# ASCII_15_BoardPowerSupply.net
KiCad netlist of a schematic drawn in Altium Designer
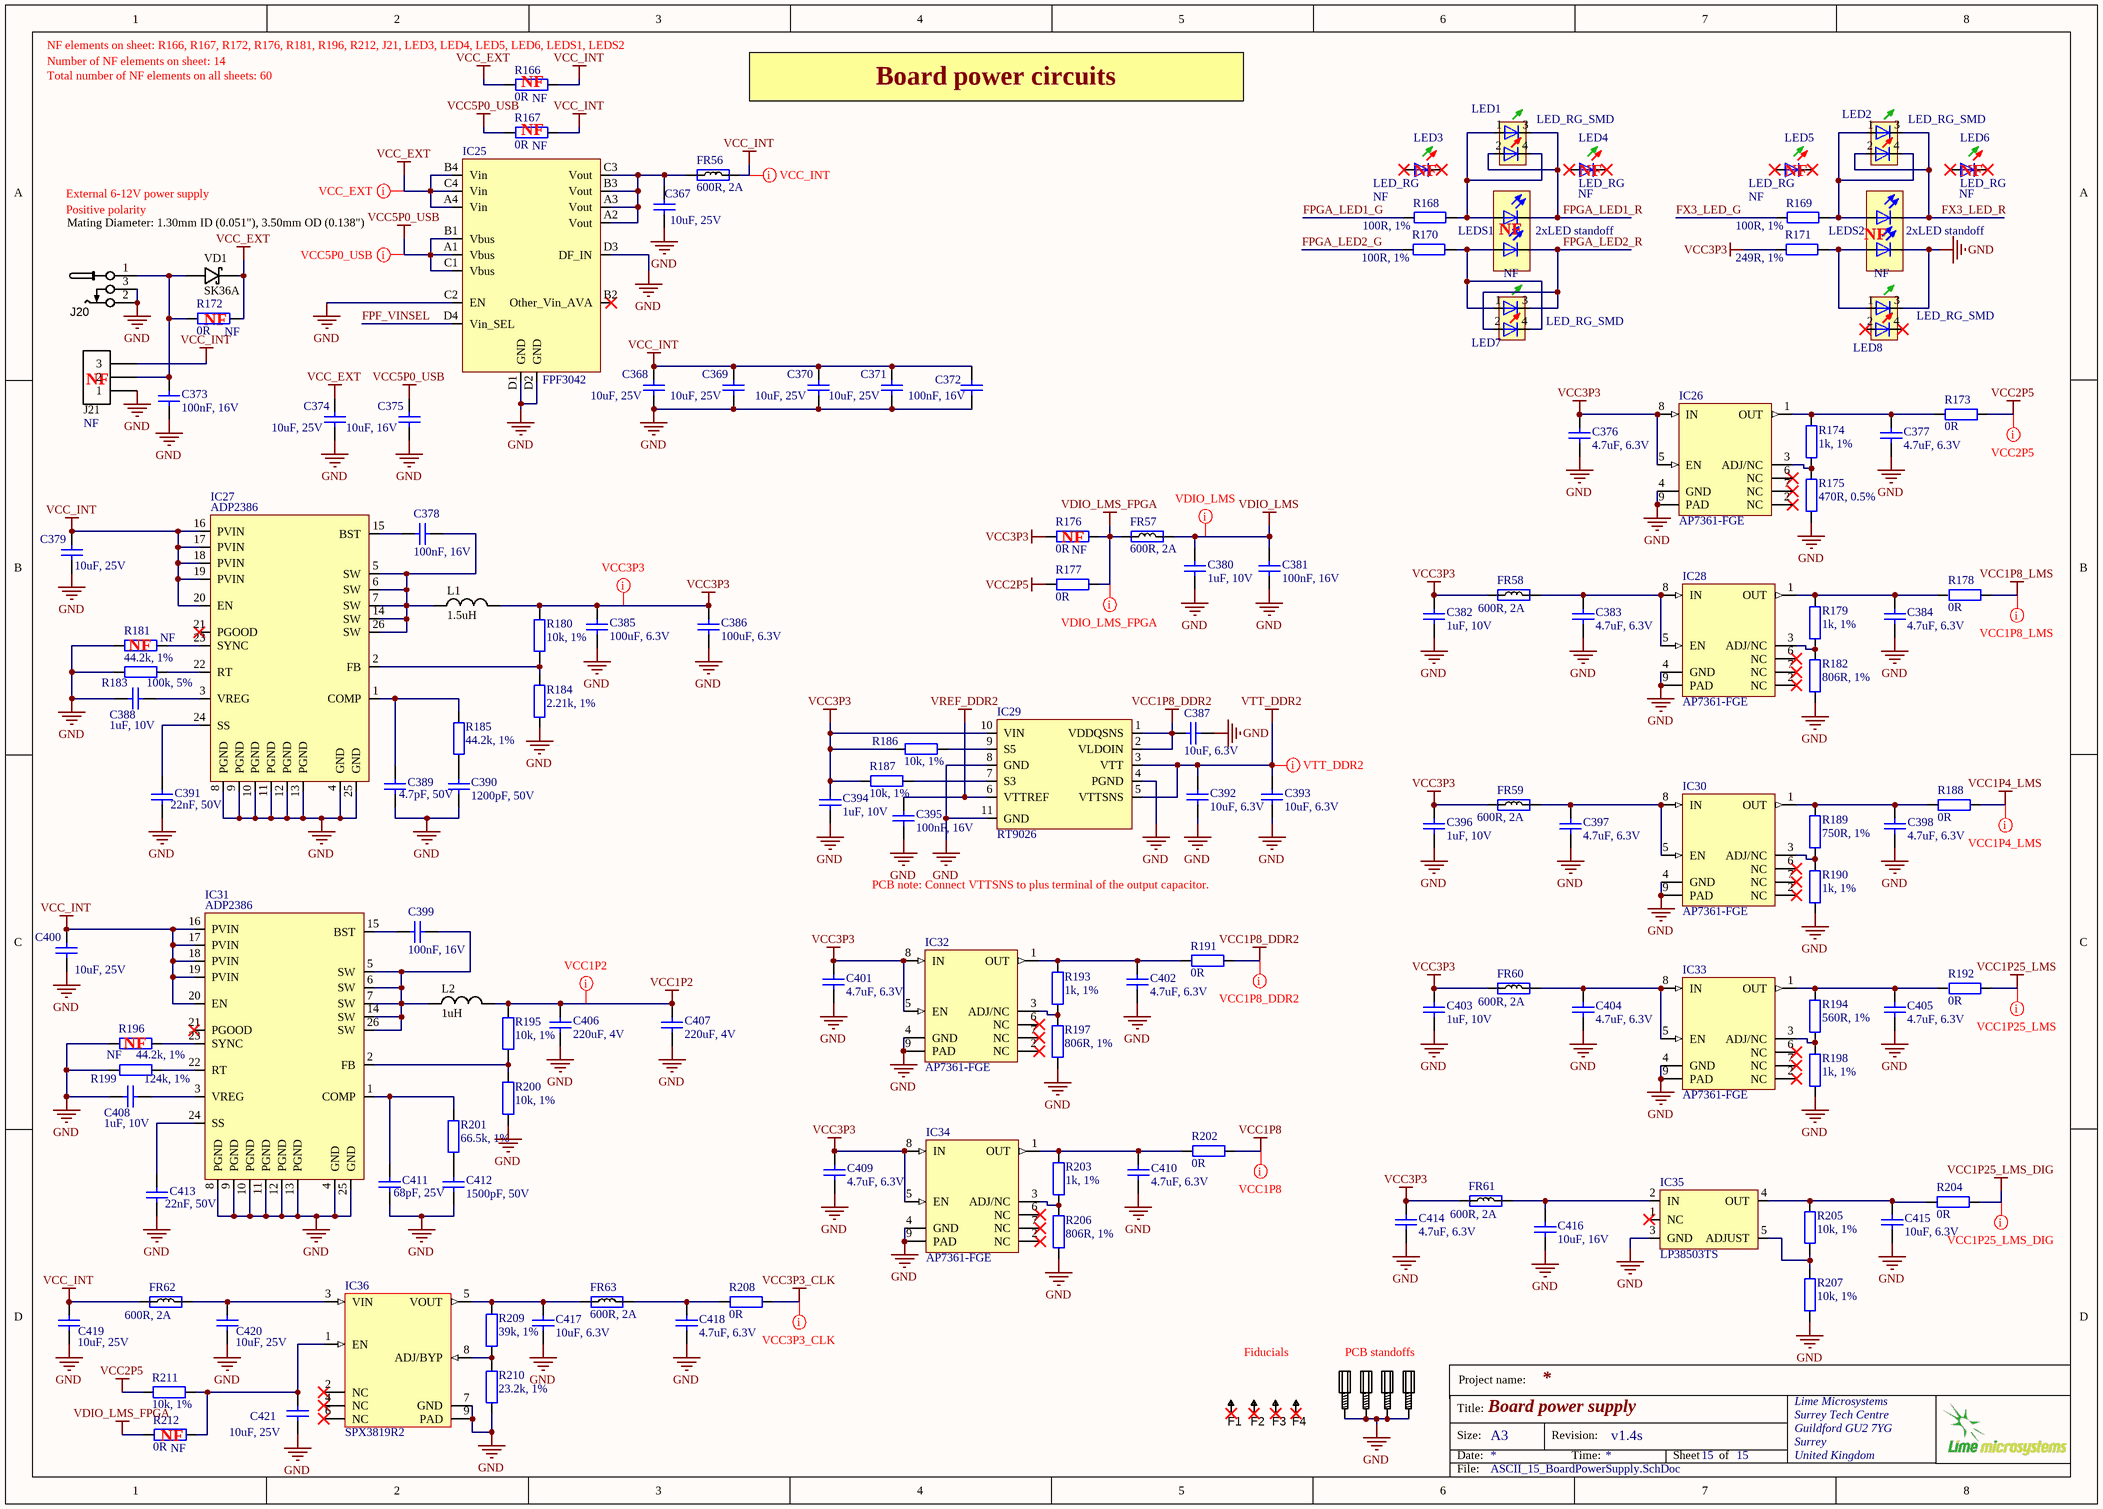
[diagram p0: ASCII_15_BoardPowerSupply.SchDoc]

(export (version "E")
  (design (tool "Eeschema 10.0.6"))
  (components
    (comp (ref "C367")
      (value "10uF, 25V")
      (footprint "CAP0603")
      (fields
        (field (name "MANUFACTURER") "Murata Electronics North America")
        (field (name "MANUFACTURER PART NUMBER") "GRM188R61E106MA73D")
        (field (name "TOLERANCE") "±20%")
      )
      (libsource (lib "LimeMicroAltiumLib_schLib") (part "Cap_0603"))
    )
    (comp (ref "C368")
      (value "10uF, 25V")
      (footprint "CAP0603")
      (fields
        (field (name "MANUFACTURER") "Murata Electronics North America")
        (field (name "MANUFACTURER PART NUMBER") "GRM188R61E106MA73D")
        (field (name "TOLERANCE") "±20%")
      )
      (libsource (lib "LimeMicroAltiumLib_schLib") (part "Cap_0603"))
    )
    (comp (ref "C369")
      (value "10uF, 25V")
      (footprint "CAP0603")
      (fields
        (field (name "MANUFACTURER") "Murata Electronics North America")
        (field (name "MANUFACTURER PART NUMBER") "GRM188R61E106MA73D")
        (field (name "TOLERANCE") "±20%")
      )
      (libsource (lib "LimeMicroAltiumLib_schLib") (part "Cap_0603"))
    )
    (comp (ref "C370")
      (value "10uF, 25V")
      (footprint "CAP0603")
      (fields
        (field (name "MANUFACTURER") "Murata Electronics North America")
        (field (name "MANUFACTURER PART NUMBER") "GRM188R61E106MA73D")
        (field (name "TOLERANCE") "±20%")
      )
      (libsource (lib "LimeMicroAltiumLib_schLib") (part "Cap_0603"))
    )
    (comp (ref "C371")
      (value "10uF, 25V")
      (footprint "CAP0603")
      (fields
        (field (name "MANUFACTURER") "Murata Electronics North America")
        (field (name "MANUFACTURER PART NUMBER") "GRM188R61E106MA73D")
        (field (name "TOLERANCE") "±20%")
      )
      (libsource (lib "LimeMicroAltiumLib_schLib") (part "Cap_0603"))
    )
    (comp (ref "C372")
      (value "100nF, 16V")
      (footprint "CAP0402")
      (fields
        (field (name "MANUFACTURER") "Murata Electronics")
        (field (name "TOLERANCE") "10 %")
        (field (name "MANUFACTURER PART NUMBER") "GRM155R71C104KA88D")
      )
      (libsource (lib "LimeMicroAltiumLib_schLib") (part "Cap_0402"))
    )
    (comp (ref "C373")
      (value "100nF, 16V")
      (footprint "CAP0402")
      (fields
        (field (name "MANUFACTURER") "Murata Electronics")
        (field (name "TOLERANCE") "10 %")
        (field (name "MANUFACTURER PART NUMBER") "GRM155R71C104KA88D")
      )
      (libsource (lib "LimeMicroAltiumLib_schLib") (part "Cap_0402"))
    )
    (comp (ref "C374")
      (value "10uF, 25V")
      (footprint "CAP0603")
      (fields
        (field (name "MANUFACTURER") "Murata Electronics North America")
        (field (name "MANUFACTURER PART NUMBER") "GRM188R61E106MA73D")
        (field (name "TOLERANCE") "±20%")
      )
      (libsource (lib "LimeMicroAltiumLib_schLib") (part "Cap_0603"))
    )
    (comp (ref "C375")
      (value "10uF, 16V")
      (footprint "CAP0603")
      (fields (field (name "MANUFACTURER") "Yageo") (field (name "TOLERANCE") "±20%"))
      (libsource (lib "LimeMicroAltiumLib_schLib") (part "Cap_0603"))
    )
    (comp (ref "C376")
      (value "4.7uF, 6.3V")
      (footprint "CAP0402")
      (fields
        (field (name "MANUFACTURER") "Murata Electronics North America")
        (field (name "TOLERANCE") "±20%")
        (field (name "MANUFACTURER PART NUMBER") "GRM155R60J475ME87D")
      )
      (libsource (lib "LimeMicroAltiumLib_schLib") (part "Cap_0402"))
    )
    (comp (ref "C377")
      (value "4.7uF, 6.3V")
      (footprint "CAP0402")
      (fields
        (field (name "MANUFACTURER") "Murata Electronics North America")
        (field (name "TOLERANCE") "±20%")
        (field (name "MANUFACTURER PART NUMBER") "GRM155R60J475ME87D")
      )
      (libsource (lib "LimeMicroAltiumLib_schLib") (part "Cap_0402"))
    )
    (comp (ref "C378")
      (value "100nF, 16V")
      (footprint "CAP0402")
      (fields
        (field (name "MANUFACTURER") "Murata Electronics")
        (field (name "TOLERANCE") "10 %")
        (field (name "MANUFACTURER PART NUMBER") "GRM155R71C104KA88D")
      )
      (libsource (lib "LimeMicroAltiumLib_schLib") (part "Cap_0402"))
    )
    (comp (ref "C379")
      (value "10uF, 25V")
      (footprint "CAP0603")
      (fields
        (field (name "MANUFACTURER") "Murata Electronics North America")
        (field (name "MANUFACTURER PART NUMBER") "GRM188R61E106MA73D")
        (field (name "TOLERANCE") "±20%")
      )
      (libsource (lib "LimeMicroAltiumLib_schLib") (part "Cap_0603"))
    )
    (comp (ref "C380")
      (value "1uF, 10V")
      (footprint "CAP0402")
      (fields (field (name "MANUFACTURER") "TDK"))
      (libsource (lib "LimeMicroAltiumLib_schLib") (part "Cap_0402"))
    )
    (comp (ref "C381")
      (value "100nF, 16V")
      (footprint "CAP0402")
      (fields
        (field (name "MANUFACTURER") "Murata Electronics")
        (field (name "TOLERANCE") "10 %")
        (field (name "MANUFACTURER PART NUMBER") "GRM155R71C104KA88D")
      )
      (libsource (lib "LimeMicroAltiumLib_schLib") (part "Cap_0402"))
    )
    (comp (ref "C382")
      (value "1uF, 10V")
      (footprint "CAP0402")
      (fields (field (name "MANUFACTURER") "TDK"))
      (libsource (lib "LimeMicroAltiumLib_schLib") (part "Cap_0402"))
    )
    (comp (ref "C383")
      (value "4.7uF, 6.3V")
      (footprint "CAP0402")
      (fields
        (field (name "MANUFACTURER") "Murata Electronics North America")
        (field (name "TOLERANCE") "±20%")
        (field (name "MANUFACTURER PART NUMBER") "GRM155R60J475ME87D")
      )
      (libsource (lib "LimeMicroAltiumLib_schLib") (part "Cap_0402"))
    )
    (comp (ref "C384")
      (value "4.7uF, 6.3V")
      (footprint "CAP0402")
      (fields
        (field (name "MANUFACTURER") "Murata Electronics North America")
        (field (name "TOLERANCE") "±20%")
        (field (name "MANUFACTURER PART NUMBER") "GRM155R60J475ME87D")
      )
      (libsource (lib "LimeMicroAltiumLib_schLib") (part "Cap_0402"))
    )
    (comp (ref "C385")
      (value "100uF, 6.3V")
      (footprint "CAP1206")
      (fields (field (name "MANUFACTURER") "Murata Electronics North America"))
      (libsource (lib "LimeFPGAboard_schLib") (part "Cap_1206"))
    )
    (comp (ref "C386")
      (value "100uF, 6.3V")
      (footprint "CAP1206")
      (fields (field (name "MANUFACTURER") "Murata Electronics North America"))
      (libsource (lib "LimeFPGAboard_schLib") (part "Cap_1206"))
    )
    (comp (ref "C387")
      (value "10uF, 6.3V")
      (footprint "CAP0603")
      (fields (field (name "TOLERANCE") "±20%") (field (name "MANUFACTURER") "Yageo"))
      (libsource (lib "LimeFPGAboard_schLib") (part "Cap_0603"))
    )
    (comp (ref "C388")
      (value "1uF, 10V")
      (footprint "CAP0402")
      (fields (field (name "MANUFACTURER") "TDK"))
      (libsource (lib "LimeMicroAltiumLib_schLib") (part "Cap_0402"))
    )
    (comp (ref "C389")
      (value "4.7pF, 50V")
      (footprint "CAP0402")
      (fields (field (name "MANUFACTURER") "Murata Electronics North America"))
      (libsource (lib "LimeMicroAltiumLib_schLib") (part "Cap_0402"))
    )
    (comp (ref "C390")
      (value "1200pF, 50V")
      (footprint "CAP0402")
      (fields (field (name "MANUFACTURER") "Kemet") (field (name "TOLERANCE") "±5%"))
      (libsource (lib "LimeMicroAltiumLib_schLib") (part "Cap_0402"))
    )
    (comp (ref "C391")
      (value "22nF, 50V")
      (footprint "CAP0402")
      (fields (field (name "TOLERANCE") "±10%") (field (name "MANUFACTURER") "Kemet"))
      (libsource (lib "LimeMicroAltiumLib_schLib") (part "Cap_0402"))
    )
    (comp (ref "C392")
      (value "10uF, 6.3V")
      (footprint "CAP0603")
      (fields (field (name "TOLERANCE") "±20%") (field (name "MANUFACTURER") "Yageo"))
      (libsource (lib "LimeFPGAboard_schLib") (part "Cap_0603"))
    )
    (comp (ref "C393")
      (value "10uF, 6.3V")
      (footprint "CAP0603")
      (fields (field (name "TOLERANCE") "±20%") (field (name "MANUFACTURER") "Yageo"))
      (libsource (lib "LimeFPGAboard_schLib") (part "Cap_0603"))
    )
    (comp (ref "C394")
      (value "1uF, 10V")
      (footprint "CAP0402")
      (fields (field (name "MANUFACTURER") "TDK"))
      (libsource (lib "LimeMicroAltiumLib_schLib") (part "Cap_0402"))
    )
    (comp (ref "C395")
      (value "100nF, 16V")
      (footprint "CAP0402")
      (fields
        (field (name "MANUFACTURER") "Murata Electronics")
        (field (name "TOLERANCE") "10 %")
        (field (name "MANUFACTURER PART NUMBER") "GRM155R71C104KA88D")
      )
      (libsource (lib "LimeMicroAltiumLib_schLib") (part "Cap_0402"))
    )
    (comp (ref "C396")
      (value "1uF, 10V")
      (footprint "CAP0402")
      (fields (field (name "MANUFACTURER") "TDK"))
      (libsource (lib "LimeMicroAltiumLib_schLib") (part "Cap_0402"))
    )
    (comp (ref "C397")
      (value "4.7uF, 6.3V")
      (footprint "CAP0402")
      (fields
        (field (name "MANUFACTURER") "Murata Electronics North America")
        (field (name "TOLERANCE") "±20%")
        (field (name "MANUFACTURER PART NUMBER") "GRM155R60J475ME87D")
      )
      (libsource (lib "LimeMicroAltiumLib_schLib") (part "Cap_0402"))
    )
    (comp (ref "C398")
      (value "4.7uF, 6.3V")
      (footprint "CAP0402")
      (fields
        (field (name "MANUFACTURER") "Murata Electronics North America")
        (field (name "TOLERANCE") "±20%")
        (field (name "MANUFACTURER PART NUMBER") "GRM155R60J475ME87D")
      )
      (libsource (lib "LimeMicroAltiumLib_schLib") (part "Cap_0402"))
    )
    (comp (ref "C399")
      (value "100nF, 16V")
      (footprint "CAP0402")
      (fields
        (field (name "MANUFACTURER") "Murata Electronics")
        (field (name "TOLERANCE") "10 %")
        (field (name "MANUFACTURER PART NUMBER") "GRM155R71C104KA88D")
      )
      (libsource (lib "LimeMicroAltiumLib_schLib") (part "Cap_0402"))
    )
    (comp (ref "C400")
      (value "10uF, 25V")
      (footprint "CAP0603")
      (fields
        (field (name "MANUFACTURER") "Murata Electronics North America")
        (field (name "MANUFACTURER PART NUMBER") "GRM188R61E106MA73D")
        (field (name "TOLERANCE") "±20%")
      )
      (libsource (lib "LimeMicroAltiumLib_schLib") (part "Cap_0603"))
    )
    (comp (ref "C401")
      (value "4.7uF, 6.3V")
      (footprint "CAP0402")
      (fields
        (field (name "MANUFACTURER") "Murata Electronics North America")
        (field (name "TOLERANCE") "±20%")
        (field (name "MANUFACTURER PART NUMBER") "GRM155R60J475ME87D")
      )
      (libsource (lib "LimeMicroAltiumLib_schLib") (part "Cap_0402"))
    )
    (comp (ref "C402")
      (value "4.7uF, 6.3V")
      (footprint "CAP0402")
      (fields
        (field (name "MANUFACTURER") "Murata Electronics North America")
        (field (name "TOLERANCE") "±20%")
        (field (name "MANUFACTURER PART NUMBER") "GRM155R60J475ME87D")
      )
      (libsource (lib "LimeMicroAltiumLib_schLib") (part "Cap_0402"))
    )
    (comp (ref "C403")
      (value "1uF, 10V")
      (footprint "CAP0402")
      (fields (field (name "MANUFACTURER") "TDK"))
      (libsource (lib "LimeMicroAltiumLib_schLib") (part "Cap_0402"))
    )
    (comp (ref "C404")
      (value "4.7uF, 6.3V")
      (footprint "CAP0402")
      (fields
        (field (name "MANUFACTURER") "Murata Electronics North America")
        (field (name "TOLERANCE") "±20%")
        (field (name "MANUFACTURER PART NUMBER") "GRM155R60J475ME87D")
      )
      (libsource (lib "LimeMicroAltiumLib_schLib") (part "Cap_0402"))
    )
    (comp (ref "C405")
      (value "4.7uF, 6.3V")
      (footprint "CAP0402")
      (fields
        (field (name "MANUFACTURER") "Murata Electronics North America")
        (field (name "TOLERANCE") "±20%")
        (field (name "MANUFACTURER PART NUMBER") "GRM155R60J475ME87D")
      )
      (libsource (lib "LimeMicroAltiumLib_schLib") (part "Cap_0402"))
    )
    (comp (ref "C406")
      (value "220uF, 4V")
      (footprint "CAP1206")
      (fields
        (field (name "MANUFACTURER") "Murata Electronics North America")
        (field (name "TOLERANCE") "±20%")
        (field (name "MANUFACTURER PART NUMBER") "GRM31CR60G227ME11L")
      )
      (libsource (lib "LimeFPGAboard_schLib") (part "Cap_1206"))
    )
    (comp (ref "C407")
      (value "220uF, 4V")
      (footprint "CAP1206")
      (fields
        (field (name "MANUFACTURER") "Murata Electronics North America")
        (field (name "TOLERANCE") "±20%")
        (field (name "MANUFACTURER PART NUMBER") "GRM31CR60G227ME11L")
      )
      (libsource (lib "LimeFPGAboard_schLib") (part "Cap_1206"))
    )
    (comp (ref "C408")
      (value "1uF, 10V")
      (footprint "CAP0402")
      (fields (field (name "MANUFACTURER") "TDK"))
      (libsource (lib "LimeMicroAltiumLib_schLib") (part "Cap_0402"))
    )
    (comp (ref "C409")
      (value "4.7uF, 6.3V")
      (footprint "CAP0402")
      (fields
        (field (name "MANUFACTURER") "Murata Electronics North America")
        (field (name "TOLERANCE") "±20%")
        (field (name "MANUFACTURER PART NUMBER") "GRM155R60J475ME87D")
      )
      (libsource (lib "LimeMicroAltiumLib_schLib") (part "Cap_0402"))
    )
    (comp (ref "C410")
      (value "4.7uF, 6.3V")
      (footprint "CAP0402")
      (fields
        (field (name "MANUFACTURER") "Murata Electronics North America")
        (field (name "TOLERANCE") "±20%")
        (field (name "MANUFACTURER PART NUMBER") "GRM155R60J475ME87D")
      )
      (libsource (lib "LimeMicroAltiumLib_schLib") (part "Cap_0402"))
    )
    (comp (ref "C411")
      (value "68pF, 25V")
      (footprint "CAP0402")
      (fields (field (name "TOLERANCE") "±1%") (field (name "MANUFACTURER") "Kemet"))
      (libsource (lib "LimeMicroAltiumLib_schLib") (part "Cap_0402"))
    )
    (comp (ref "C412")
      (value "1500pF, 50V")
      (footprint "CAP0402")
      (fields
        (field (name "MANUFACTURER") "Samsung Electro-Mechanics America, Inc.")
        (field (name "TOLERANCE") "±10%")
      )
      (libsource (lib "LimeMicroAltiumLib_schLib") (part "Cap_0402"))
    )
    (comp (ref "C413")
      (value "22nF, 50V")
      (footprint "CAP0402")
      (fields (field (name "TOLERANCE") "±10%") (field (name "MANUFACTURER") "Kemet"))
      (libsource (lib "LimeMicroAltiumLib_schLib") (part "Cap_0402"))
    )
    (comp (ref "C414")
      (value "4.7uF, 6.3V")
      (footprint "CAP0402")
      (fields
        (field (name "MANUFACTURER") "Murata Electronics North America")
        (field (name "TOLERANCE") "±20%")
        (field (name "MANUFACTURER PART NUMBER") "GRM155R60J475ME87D")
      )
      (libsource (lib "LimeMicroAltiumLib_schLib") (part "Cap_0402"))
    )
    (comp (ref "C415")
      (value "10uF, 6.3V")
      (footprint "CAP0603")
      (fields (field (name "TOLERANCE") "±20%") (field (name "MANUFACTURER") "Yageo"))
      (libsource (lib "LimeFPGAboard_schLib") (part "Cap_0603"))
    )
    (comp (ref "C416")
      (value "10uF, 16V")
      (footprint "CAP0603")
      (fields (field (name "MANUFACTURER") "Yageo") (field (name "TOLERANCE") "±20%"))
      (libsource (lib "LimeMicroAltiumLib_schLib") (part "Cap_0603"))
    )
    (comp (ref "C417")
      (value "10uF, 6.3V")
      (footprint "CAP0603")
      (fields (field (name "TOLERANCE") "±20%") (field (name "MANUFACTURER") "Yageo"))
      (libsource (lib "LimeFPGAboard_schLib") (part "Cap_0603"))
    )
    (comp (ref "C418")
      (value "4.7uF, 6.3V")
      (footprint "CAP0402")
      (fields
        (field (name "MANUFACTURER") "Murata Electronics North America")
        (field (name "TOLERANCE") "±20%")
        (field (name "MANUFACTURER PART NUMBER") "GRM155R60J475ME87D")
      )
      (libsource (lib "LimeMicroAltiumLib_schLib") (part "Cap_0402"))
    )
    (comp (ref "C419")
      (value "10uF, 25V")
      (footprint "CAP0603")
      (fields
        (field (name "MANUFACTURER") "Murata Electronics North America")
        (field (name "MANUFACTURER PART NUMBER") "GRM188R61E106MA73D")
        (field (name "TOLERANCE") "±20%")
      )
      (libsource (lib "LimeMicroAltiumLib_schLib") (part "Cap_0603"))
    )
    (comp (ref "C420")
      (value "10uF, 25V")
      (footprint "CAP0603")
      (fields
        (field (name "MANUFACTURER") "Murata Electronics North America")
        (field (name "MANUFACTURER PART NUMBER") "GRM188R61E106MA73D")
        (field (name "TOLERANCE") "±20%")
      )
      (libsource (lib "LimeMicroAltiumLib_schLib") (part "Cap_0603"))
    )
    (comp (ref "C421")
      (value "10uF, 25V")
      (footprint "CAP0603")
      (fields
        (field (name "MANUFACTURER") "Murata Electronics North America")
        (field (name "MANUFACTURER PART NUMBER") "GRM188R61E106MA73D")
        (field (name "TOLERANCE") "±20%")
      )
      (libsource (lib "LimeMicroAltiumLib_schLib") (part "Cap_0603"))
    )
    (comp (ref "F1")
      (value "Fiducial")
      (footprint "Fiducial")
      (libsource (lib "VGTU_Altium_lib") (part "Fiducial"))
    )
    (comp (ref "F2")
      (value "Fiducial")
      (footprint "Fiducial")
      (libsource (lib "VGTU_Altium_lib") (part "Fiducial"))
    )
    (comp (ref "F3")
      (value "Fiducial")
      (footprint "Fiducial")
      (libsource (lib "VGTU_Altium_lib") (part "Fiducial"))
    )
    (comp (ref "F4")
      (value "Fiducial")
      (footprint "Fiducial")
      (libsource (lib "VGTU_Altium_lib") (part "Fiducial"))
    )
    (comp (ref "FR56")
      (value "600R, 2A")
      (footprint "RES0805")
      (fields (field (name "MANUFACTURER") "TDK Corporation"))
      (libsource (lib "LimeFPGAboard_schLib") (part "Ferrite"))
    )
    (comp (ref "FR57")
      (value "600R, 2A")
      (footprint "RES0805")
      (fields (field (name "MANUFACTURER") "TDK Corporation"))
      (libsource (lib "LimeMicroAltiumLib_schLib") (part "Ferrite"))
    )
    (comp (ref "FR58")
      (value "600R, 2A")
      (footprint "RES0805")
      (fields (field (name "MANUFACTURER") "TDK Corporation"))
      (libsource (lib "LimeMicroAltiumLib_schLib") (part "Ferrite"))
    )
    (comp (ref "FR59")
      (value "600R, 2A")
      (footprint "RES0805")
      (fields (field (name "MANUFACTURER") "TDK Corporation"))
      (libsource (lib "LimeMicroAltiumLib_schLib") (part "Ferrite"))
    )
    (comp (ref "FR60")
      (value "600R, 2A")
      (footprint "RES0805")
      (fields (field (name "MANUFACTURER") "TDK Corporation"))
      (libsource (lib "LimeMicroAltiumLib_schLib") (part "Ferrite"))
    )
    (comp (ref "FR61")
      (value "600R, 2A")
      (footprint "RES0805")
      (fields (field (name "MANUFACTURER") "TDK Corporation"))
      (libsource (lib "LimeMicroAltiumLib_schLib") (part "Ferrite"))
    )
    (comp (ref "FR62")
      (value "600R, 2A")
      (footprint "RES0805")
      (fields (field (name "MANUFACTURER") "TDK Corporation"))
      (libsource (lib "LimeMicroAltiumLib_schLib") (part "Ferrite"))
    )
    (comp (ref "FR63")
      (value "600R, 2A")
      (footprint "RES0805")
      (fields (field (name "MANUFACTURER") "TDK Corporation"))
      (libsource (lib "LimeMicroAltiumLib_schLib") (part "Ferrite"))
    )
    (comp (ref "IC25")
      (value "FPF3042")
      (footprint "FPF3042")
      (fields (field (name "MANUFACTURER") "Fairchild Semiconductor"))
      (libsource (lib "LimeMicroAltiumLib_schLib") (part "FPF3042"))
    )
    (comp (ref "IC26")
      (value "AP7361-FGE")
      (footprint "AP7361")
      (fields
        (field (name "MANUFACTURER PART NUMBER") "AP7361-FGE-7")
        (field (name "MANUFACTURER") "Diodes Incorporated")
      )
      (libsource (lib "LimeMicroAltiumLib_schLib") (part "AP7361"))
    )
    (comp (ref "IC27")
      (value "ADP2386")
      (footprint "ADP2386")
      (fields
        (field (name "MANUFACTURER PART NUMBER") "ADP2386ACPZN-R7")
        (field (name "MANUFACTURER") "Analog Devices Inc.")
      )
      (libsource (lib "LimeMicroAltiumLib_schLib") (part "ADP2386"))
    )
    (comp (ref "IC28")
      (value "AP7361-FGE")
      (footprint "AP7361")
      (fields
        (field (name "MANUFACTURER PART NUMBER") "AP7361-FGE-7")
        (field (name "MANUFACTURER") "Diodes Incorporated")
      )
      (libsource (lib "LimeMicroAltiumLib_schLib") (part "AP7361"))
    )
    (comp (ref "IC29")
      (value "RT9026")
      (footprint "MSOP10")
      (fields (field (name "MANUFACTURER") "Richtek USA Inc."))
      (libsource (lib "LimeMicroAltiumLib_schLib") (part "RT9026"))
    )
    (comp (ref "IC30")
      (value "AP7361-FGE")
      (footprint "AP7361")
      (fields
        (field (name "MANUFACTURER PART NUMBER") "AP7361-FGE-7")
        (field (name "MANUFACTURER") "Diodes Incorporated")
      )
      (libsource (lib "LimeMicroAltiumLib_schLib") (part "AP7361"))
    )
    (comp (ref "IC31")
      (value "ADP2386")
      (footprint "ADP2386")
      (fields (field (name "MANUFACTURER") "Analog Devices Inc."))
      (libsource (lib "LimeMicroAltiumLib_schLib") (part "ADP2386"))
    )
    (comp (ref "IC32")
      (value "AP7361-FGE")
      (footprint "AP7361")
      (fields
        (field (name "MANUFACTURER PART NUMBER") "AP7361-FGE-7")
        (field (name "MANUFACTURER") "Diodes Incorporated")
      )
      (libsource (lib "LimeMicroAltiumLib_schLib") (part "AP7361"))
    )
    (comp (ref "IC33")
      (value "AP7361-FGE")
      (footprint "AP7361")
      (fields
        (field (name "MANUFACTURER PART NUMBER") "AP7361-FGE-7")
        (field (name "MANUFACTURER") "Diodes Incorporated")
      )
      (libsource (lib "LimeMicroAltiumLib_schLib") (part "AP7361"))
    )
    (comp (ref "IC34")
      (value "AP7361-FGE")
      (footprint "AP7361")
      (fields
        (field (name "MANUFACTURER PART NUMBER") "AP7361-FGE-7")
        (field (name "MANUFACTURER") "Diodes Incorporated")
      )
      (libsource (lib "LimeMicroAltiumLib_schLib") (part "AP7361"))
    )
    (comp (ref "IC35")
      (value "LP38503TS")
      (footprint "TO-263-5_v2")
      (fields
        (field (name "MANUFACTURER PART NUMBER") "LP38503TS-ADJ/NOPB")
        (field (name "MANUFACTURER") "Texas Instruments")
      )
      (libsource (lib "LimeMicroAltiumLib_schLib") (part "LP38503TS"))
    )
    (comp (ref "IC36")
      (value "SPX3819R2")
      (footprint "SPX3819R2-L/TR")
      (fields (field (name "MANUFACTURER") "Exar Corporation"))
      (libsource (lib "LimeMicroAltiumLib_schLib") (part "SPX3819R2-L/TR"))
    )
    (comp (ref "J20")
      (value "Mating Diameter: 1.30mm ID (0.051\"), 3.50mm OD (0.138\")")
      (footprint "CONN_PWR_JACK_v4")
      (fields (field (name "MANUFACTURER") "CUI Inc."))
      (libsource (lib "LimeFPGAboard_schLib") (part "CONN_PWR_JACK_2.1x5.5mm"))
    )
    (comp (ref "J21")
      (value "Header 3x1 pin")
      (footprint "HDR_1x3")
      (description "Header, 3-pin")
      (fields (field (name "ASSEMBLY INFO") "NF") (field (name "MANUFACTURER") "Amphenol FCI"))
      (libsource (lib "LimeMicroAltiumLib_schLib") (part "Header3P"))
    )
    (comp (ref "L1")
      (value "1.5uH")
      (footprint "FDVE1040_TOKO_INDUCTOR")
      (fields (field (name "MANUFACTURER") "Vishay Dale") (field (name "TOLERANCE") "±20%"))
      (libsource (lib "LimeMicroAltiumLib_schLib") (part "Inductor_0603"))
    )
    (comp (ref "L2")
      (value "1uH")
      (footprint "FDVE1040_TOKO_INDUCTOR")
      (fields (field (name "TOLERANCE") "±20%") (field (name "MANUFACTURER") "Vishay Dale"))
      (libsource (lib "LimeMicroAltiumLib_schLib") (part "Inductor_0603"))
    )
    (comp (ref "LED1")
      (value "LED_RG_SMD")
      (footprint "LED-2x0603")
      (fields (field (name "MANUFACTURER") "Avago Technologies US Inc."))
      (libsource (lib "LimeMicroAltiumLib_schLib") (part "LED_green_red_SMD"))
    )
    (comp (ref "LED2")
      (value "LED_RG_SMD")
      (footprint "LED-2x0603")
      (fields (field (name "MANUFACTURER") "Avago Technologies US Inc."))
      (libsource (lib "LimeMicroAltiumLib_schLib") (part "LED_green_red_SMD"))
    )
    (comp (ref "LED3")
      (value "LED_RG")
      (fields
        (field (name "MANUFACTURER") "Visual Communications Company - VCC")
        (field (name "ASSEMBLY INFO") "NF")
      )
      (libsource (lib "LimeMicroAltiumLib_schLib") (part "LED_green_red"))
    )
    (comp (ref "LED4")
      (value "LED_RG")
      (fields
        (field (name "MANUFACTURER") "Visual Communications Company - VCC")
        (field (name "ASSEMBLY INFO") "NF")
      )
      (libsource (lib "LimeMicroAltiumLib_schLib") (part "LED_green_red"))
    )
    (comp (ref "LED5")
      (value "LED_RG")
      (fields
        (field (name "MANUFACTURER") "Visual Communications Company - VCC")
        (field (name "ASSEMBLY INFO") "NF")
      )
      (libsource (lib "LimeMicroAltiumLib_schLib") (part "LED_green_red"))
    )
    (comp (ref "LED6")
      (value "LED_RG")
      (fields
        (field (name "MANUFACTURER") "Visual Communications Company - VCC")
        (field (name "ASSEMBLY INFO") "NF")
      )
      (libsource (lib "LimeMicroAltiumLib_schLib") (part "LED_green_red"))
    )
    (comp (ref "LED7")
      (value "LED_RG_SMD")
      (footprint "LED-2x0603")
      (fields (field (name "MANUFACTURER") "Avago Technologies US Inc."))
      (libsource (lib "LimeMicroAltiumLib_schLib") (part "LED_green_red_SMD"))
    )
    (comp (ref "LED8")
      (value "LED_RG_SMD")
      (footprint "LED-2x0603")
      (fields (field (name "MANUFACTURER") "Avago Technologies US Inc."))
      (libsource (lib "LimeMicroAltiumLib_schLib") (part "LED_green_red_SMD"))
    )
    (comp (ref "LEDS1")
      (value "2xLED standoff")
      (footprint "LED_STANDOFF_H-201C")
      (fields (field (name "MANUFACTURER") "Bivar Inc.") (field (name "ASSEMBLY INFO") "NF"))
      (libsource (lib "LimeMicroAltiumLib_schLib") (part "LEDx2_STANDOFF"))
    )
    (comp (ref "LEDS2")
      (value "2xLED standoff")
      (footprint "LED_STANDOFF_H-201C")
      (fields (field (name "MANUFACTURER") "Bivar Inc.") (field (name "ASSEMBLY INFO") "NF"))
      (libsource (lib "LimeMicroAltiumLib_schLib") (part "LEDx2_STANDOFF"))
    )
    (comp (ref "MECH1")
      (value "# pcs.")
      (footprint "PCB_standoff")
      (description "STANDOFF M/F MET 5MM HEX 10MM L")
      (fields (field (name "MANUFACTURER") "FIX&FASTEN"))
      (libsource (lib "LimeMicroAltiumLib_schLib") (part "STANDOFF_M-F_THREADED_M3x8x10mm_HEX_5mm dia"))
    )
    (comp (ref "MECH2")
      (value "# pcs.")
      (footprint "PCB_standoff")
      (description "STANDOFF M/F MET 5MM HEX 10MM L")
      (fields (field (name "MANUFACTURER") "FIX&FASTEN"))
      (libsource (lib "LimeMicroAltiumLib_schLib") (part "STANDOFF_M-F_THREADED_M3x8x10mm_HEX_5mm dia"))
    )
    (comp (ref "MECH3")
      (value "# pcs.")
      (footprint "PCB_standoff")
      (description "STANDOFF M/F MET 5MM HEX 10MM L")
      (fields (field (name "MANUFACTURER") "FIX&FASTEN"))
      (libsource (lib "LimeMicroAltiumLib_schLib") (part "STANDOFF_M-F_THREADED_M3x8x10mm_HEX_5mm dia"))
    )
    (comp (ref "MECH4")
      (value "# pcs.")
      (footprint "PCB_standoff")
      (description "STANDOFF M/F MET 5MM HEX 10MM L")
      (fields (field (name "MANUFACTURER") "FIX&FASTEN"))
      (libsource (lib "LimeMicroAltiumLib_schLib") (part "STANDOFF_M-F_THREADED_M3x8x10mm_HEX_5mm dia"))
    )
    (comp (ref "R166")
      (value "0R")
      (footprint "RES0402")
      (fields
        (field (name "ASSEMBLY INFO") "NF")
        (field (name "MANUFACTURER") "Yageo")
        (field (name "TOLERANCE") "Jumper")
      )
      (libsource (lib "LimeMicroAltiumLib_schLib") (part "Res_0402"))
    )
    (comp (ref "R167")
      (value "0R")
      (footprint "RES0402")
      (fields
        (field (name "ASSEMBLY INFO") "NF")
        (field (name "MANUFACTURER") "Yageo")
        (field (name "TOLERANCE") "Jumper")
      )
      (libsource (lib "LimeMicroAltiumLib_schLib") (part "Res_0402"))
    )
    (comp (ref "R168")
      (value "100R, 1%")
      (footprint "RES0402")
      (fields (field (name "TOLERANCE") "±1%") (field (name "MANUFACTURER") "Stackpole Electronics Inc."))
      (libsource (lib "LimeMicroAltiumLib_schLib") (part "Res_0402"))
    )
    (comp (ref "R169")
      (value "100R, 1%")
      (footprint "RES0402")
      (fields (field (name "TOLERANCE") "±1%") (field (name "MANUFACTURER") "Stackpole Electronics Inc."))
      (libsource (lib "LimeMicroAltiumLib_schLib") (part "Res_0402"))
    )
    (comp (ref "R170")
      (value "100R, 1%")
      (footprint "RES0402")
      (fields (field (name "TOLERANCE") "±1%") (field (name "MANUFACTURER") "Stackpole Electronics Inc."))
      (libsource (lib "LimeMicroAltiumLib_schLib") (part "Res_0402"))
    )
    (comp (ref "R171")
      (value "249R, 1%")
      (footprint "RES0402")
      (fields (field (name "MANUFACTURER") "Stackpole Electronics Inc") (field (name "TOLERANCE") "±1%"))
      (libsource (lib "LimeMicroAltiumLib_schLib") (part "Res_0402"))
    )
    (comp (ref "R172")
      (value "0R")
      (footprint "RES0805")
      (fields
        (field (name "ASSEMBLY INFO") "NF")
        (field (name "MANUFACTURER") "Vishay Dale")
        (field (name "TOLERANCE") "Jumper")
      )
      (libsource (lib "LimeMicroAltiumLib_schLib") (part "Res_0402"))
    )
    (comp (ref "R173")
      (value "0R")
      (footprint "RES0402")
      (fields (field (name "MANUFACTURER") "Yageo") (field (name "TOLERANCE") "Jumper"))
      (libsource (lib "LimeMicroAltiumLib_schLib") (part "Res_0402"))
    )
    (comp (ref "R174")
      (value "1k, 1%")
      (footprint "RES0402")
      (fields (field (name "MANUFACTURER") "Stackpole Electronics Inc") (field (name "TOLERANCE") "±1%"))
      (libsource (lib "LimeMicroAltiumLib_schLib") (part "Res_0402"))
    )
    (comp (ref "R175")
      (value "470R, 0.5%")
      (footprint "RES0402")
      (fields
        (field (name "TOLERANCE") "±0.5%")
        (field (name "MANUFACTURER") "Panasonic Electronic Components")
      )
      (libsource (lib "LimeMicroAltiumLib_schLib") (part "Res_0402"))
    )
    (comp (ref "R176")
      (value "0R")
      (footprint "RES0402")
      (fields
        (field (name "ASSEMBLY INFO") "NF")
        (field (name "MANUFACTURER") "Yageo")
        (field (name "TOLERANCE") "Jumper")
      )
      (libsource (lib "LimeMicroAltiumLib_schLib") (part "Res_0402"))
    )
    (comp (ref "R177")
      (value "0R")
      (footprint "RES0402")
      (fields (field (name "MANUFACTURER") "Yageo") (field (name "TOLERANCE") "Jumper"))
      (libsource (lib "LimeMicroAltiumLib_schLib") (part "Res_0402"))
    )
    (comp (ref "R178")
      (value "0R")
      (footprint "RES0402")
      (fields (field (name "MANUFACTURER") "Yageo") (field (name "TOLERANCE") "Jumper"))
      (libsource (lib "LimeMicroAltiumLib_schLib") (part "Res_0402"))
    )
    (comp (ref "R179")
      (value "1k, 1%")
      (footprint "RES0402")
      (fields (field (name "MANUFACTURER") "Stackpole Electronics Inc") (field (name "TOLERANCE") "±1%"))
      (libsource (lib "LimeMicroAltiumLib_schLib") (part "Res_0402"))
    )
    (comp (ref "R180")
      (value "10k, 1%")
      (footprint "RES0402")
      (fields (field (name "MANUFACTURER") "Yageo") (field (name "TOLERANCE") "±1%"))
      (libsource (lib "LimeMicroAltiumLib_schLib") (part "Res_0402"))
    )
    (comp (ref "R181")
      (value "44.2k, 1%")
      (footprint "RES0402")
      (fields
        (field (name "ASSEMBLY INFO") "NF")
        (field (name "TOLERANCE") "±1%")
        (field (name "MANUFACTURER") "Panasonic Electronic Components")
      )
      (libsource (lib "LimeMicroAltiumLib_schLib") (part "Res_0402"))
    )
    (comp (ref "R182")
      (value "806R, 1%")
      (footprint "RES0402")
      (fields (field (name "TOLERANCE") "±1%") (field (name "MANUFACTURER") "Stackpole Electronics Inc"))
      (libsource (lib "LimeMicroAltiumLib_schLib") (part "Res_0402"))
    )
    (comp (ref "R183")
      (value "100k, 5%")
      (footprint "RES0402")
      (fields
        (field (name "MANUFACTURER") "Panasonic Electronic Components")
        (field (name "MANUFACTURER PART NUMBER") "ERJ-2GEJ104X")
        (field (name "TOLERANCE") "±5%")
      )
      (libsource (lib "LimeMicroAltiumLib_schLib") (part "Res_0402"))
    )
    (comp (ref "R184")
      (value "2.21k, 1%")
      (footprint "RES0402")
      (fields (field (name "MANUFACTURER") "Stackpole Electronics Inc.") (field (name "TOLERANCE") "±1%"))
      (libsource (lib "LimeMicroAltiumLib_schLib") (part "Res_0402"))
    )
    (comp (ref "R185")
      (value "44.2k, 1%")
      (footprint "RES0402")
      (fields
        (field (name "TOLERANCE") "±1%")
        (field (name "MANUFACTURER") "Panasonic Electronic Components")
      )
      (libsource (lib "LimeMicroAltiumLib_schLib") (part "Res_0402"))
    )
    (comp (ref "R186")
      (value "10k, 1%")
      (footprint "RES0402")
      (fields (field (name "MANUFACTURER") "Yageo") (field (name "TOLERANCE") "±1%"))
      (libsource (lib "LimeMicroAltiumLib_schLib") (part "Res_0402"))
    )
    (comp (ref "R187")
      (value "10k, 1%")
      (footprint "RES0402")
      (fields (field (name "MANUFACTURER") "Yageo") (field (name "TOLERANCE") "±1%"))
      (libsource (lib "LimeMicroAltiumLib_schLib") (part "Res_0402"))
    )
    (comp (ref "R188")
      (value "0R")
      (footprint "RES0402")
      (fields (field (name "MANUFACTURER") "Yageo") (field (name "TOLERANCE") "Jumper"))
      (libsource (lib "LimeMicroAltiumLib_schLib") (part "Res_0402"))
    )
    (comp (ref "R189")
      (value "750R, 1%")
      (footprint "RES0402")
      (fields
        (field (name "TOLERANCE") "±1%")
        (field (name "MANUFACTURER PART NUMBER") "RC0402FR-07750RL")
        (field (name "MANUFACTURER") "Yageo")
      )
      (libsource (lib "LimeMicroAltiumLib_schLib") (part "Res_0402"))
    )
    (comp (ref "R190")
      (value "1k, 1%")
      (footprint "RES0402")
      (fields (field (name "MANUFACTURER") "Stackpole Electronics Inc") (field (name "TOLERANCE") "±1%"))
      (libsource (lib "LimeMicroAltiumLib_schLib") (part "Res_0402"))
    )
    (comp (ref "R191")
      (value "0R")
      (footprint "RES0402")
      (fields (field (name "MANUFACTURER") "Yageo") (field (name "TOLERANCE") "Jumper"))
      (libsource (lib "LimeMicroAltiumLib_schLib") (part "Res_0402"))
    )
    (comp (ref "R192")
      (value "0R")
      (footprint "RES0402")
      (fields (field (name "MANUFACTURER") "Yageo") (field (name "TOLERANCE") "Jumper"))
      (libsource (lib "LimeMicroAltiumLib_schLib") (part "Res_0402"))
    )
    (comp (ref "R193")
      (value "1k, 1%")
      (footprint "RES0402")
      (fields (field (name "MANUFACTURER") "Stackpole Electronics Inc") (field (name "TOLERANCE") "±1%"))
      (libsource (lib "LimeMicroAltiumLib_schLib") (part "Res_0402"))
    )
    (comp (ref "R194")
      (value "560R, 1%")
      (footprint "RES0402")
      (fields
        (field (name "MANUFACTURER PART NUMBER") "CRCW0402560RFKED")
        (field (name "TOLERANCE") "±1%")
        (field (name "MANUFACTURER") "Vishay Dale")
      )
      (libsource (lib "LimeMicroAltiumLib_schLib") (part "Res_0402"))
    )
    (comp (ref "R195")
      (value "10k, 1%")
      (footprint "RES0402")
      (fields (field (name "MANUFACTURER") "Yageo") (field (name "TOLERANCE") "±1%"))
      (libsource (lib "LimeMicroAltiumLib_schLib") (part "Res_0402"))
    )
    (comp (ref "R196")
      (value "44.2k, 1%")
      (footprint "RES0402")
      (fields
        (field (name "ASSEMBLY INFO") "NF")
        (field (name "TOLERANCE") "±1%")
        (field (name "MANUFACTURER") "Panasonic Electronic Components")
      )
      (libsource (lib "LimeMicroAltiumLib_schLib") (part "Res_0402"))
    )
    (comp (ref "R197")
      (value "806R, 1%")
      (footprint "RES0402")
      (fields (field (name "TOLERANCE") "±1%") (field (name "MANUFACTURER") "Stackpole Electronics Inc"))
      (libsource (lib "LimeMicroAltiumLib_schLib") (part "Res_0402"))
    )
    (comp (ref "R198")
      (value "1k, 1%")
      (footprint "RES0402")
      (fields (field (name "MANUFACTURER") "Stackpole Electronics Inc") (field (name "TOLERANCE") "±1%"))
      (libsource (lib "LimeMicroAltiumLib_schLib") (part "Res_0402"))
    )
    (comp (ref "R199")
      (value "124k, 1%")
      (footprint "RES0402")
      (fields
        (field (name "MANUFACTURER") "Panasonic Electronic Components")
        (field (name "TOLERANCE") "±1%")
      )
      (libsource (lib "LimeMicroAltiumLib_schLib") (part "Res_0402"))
    )
    (comp (ref "R200")
      (value "10k, 1%")
      (footprint "RES0402")
      (fields (field (name "MANUFACTURER") "Yageo") (field (name "TOLERANCE") "±1%"))
      (libsource (lib "LimeMicroAltiumLib_schLib") (part "Res_0402"))
    )
    (comp (ref "R201")
      (value "66.5k, 1%")
      (footprint "RES0402")
      (fields
        (field (name "MANUFACTURER") "Panasonic Electronic Components")
        (field (name "TOLERANCE") "±1%")
      )
      (libsource (lib "LimeMicroAltiumLib_schLib") (part "Res_0402"))
    )
    (comp (ref "R202")
      (value "0R")
      (footprint "RES0402")
      (fields (field (name "MANUFACTURER") "Yageo") (field (name "TOLERANCE") "Jumper"))
      (libsource (lib "LimeMicroAltiumLib_schLib") (part "Res_0402"))
    )
    (comp (ref "R203")
      (value "1k, 1%")
      (footprint "RES0402")
      (fields (field (name "MANUFACTURER") "Stackpole Electronics Inc") (field (name "TOLERANCE") "±1%"))
      (libsource (lib "LimeMicroAltiumLib_schLib") (part "Res_0402"))
    )
    (comp (ref "R204")
      (value "0R")
      (footprint "RES0402")
      (fields (field (name "MANUFACTURER") "Yageo") (field (name "TOLERANCE") "Jumper"))
      (libsource (lib "LimeMicroAltiumLib_schLib") (part "Res_0402"))
    )
    (comp (ref "R205")
      (value "10k, 1%")
      (footprint "RES0402")
      (fields (field (name "MANUFACTURER") "Yageo") (field (name "TOLERANCE") "±1%"))
      (libsource (lib "LimeMicroAltiumLib_schLib") (part "Res_0402"))
    )
    (comp (ref "R206")
      (value "806R, 1%")
      (footprint "RES0402")
      (fields (field (name "TOLERANCE") "±1%") (field (name "MANUFACTURER") "Stackpole Electronics Inc"))
      (libsource (lib "LimeMicroAltiumLib_schLib") (part "Res_0402"))
    )
    (comp (ref "R207")
      (value "10k, 1%")
      (footprint "RES0402")
      (fields (field (name "MANUFACTURER") "Yageo") (field (name "TOLERANCE") "±1%"))
      (libsource (lib "LimeMicroAltiumLib_schLib") (part "Res_0402"))
    )
    (comp (ref "R208")
      (value "0R")
      (footprint "RES0402")
      (fields (field (name "MANUFACTURER") "Yageo") (field (name "TOLERANCE") "Jumper"))
      (libsource (lib "LimeMicroAltiumLib_schLib") (part "Res_0402"))
    )
    (comp (ref "R209")
      (value "39k, 1%")
      (footprint "RES0402")
      (fields (field (name "MANUFACTURER") "Yageo") (field (name "TOLERANCE") "±1%"))
      (libsource (lib "LimeMicroAltiumLib_schLib") (part "Res_0402"))
    )
    (comp (ref "R210")
      (value "23.2k, 1%")
      (footprint "RES0402")
      (fields (field (name "TOLERANCE") "±1%") (field (name "MANUFACTURER") "Yageo"))
      (libsource (lib "LimeMicroAltiumLib_schLib") (part "Res_0402"))
    )
    (comp (ref "R211")
      (value "10k, 1%")
      (footprint "RES0402")
      (fields (field (name "MANUFACTURER") "Yageo") (field (name "TOLERANCE") "±1%"))
      (libsource (lib "LimeMicroAltiumLib_schLib") (part "Res_0402"))
    )
    (comp (ref "R212")
      (value "0R")
      (footprint "RES0402")
      (fields
        (field (name "ASSEMBLY INFO") "NF")
        (field (name "MANUFACTURER") "Yageo")
        (field (name "TOLERANCE") "Jumper")
      )
      (libsource (lib "LimeMicroAltiumLib_schLib") (part "Res_0402"))
    )
    (comp (ref "VD1")
      (value "SK36A")
      (footprint "DIODE_SMB")
      (description "Diode Schottky SMD SOD-523F")
      (fields (field (name "MANUFACTURER") "Micro Commercial Co"))
      (libsource (lib "LimeMicroAltiumLib_schLib") (part "DIODE_SCHOTTKY_SOD-523F"))
    )
  )
  (nets
    (net (code "1") (name "/FPF_VINSEL") (class "Default")
      (node (ref "IC25") (pin "D4") (pinfunction "Vin_SEL_D4") (pintype "passive"))
    )
    (net (code "2") (name "/FPGA_LED1_G") (class "Default")
      (node (ref "R168") (pin "1") (pinfunction "1_1") (pintype "passive"))
    )
    (net (code "3") (name "/FPGA_LED1_R") (class "Default")
      (node (ref "LED1") (pin "2") (pinfunction "2_2") (pintype "power_in"))
      (node (ref "LED1") (pin "3") (pinfunction "3_3") (pintype "power_in"))
      (node (ref "LEDS1") (pin "K1") (pinfunction "C_K1") (pintype "power_in"))
    )
    (net (code "4") (name "/FPGA_LED2_G") (class "Default")
      (node (ref "R170") (pin "1") (pinfunction "1_1") (pintype "passive"))
    )
    (net (code "5") (name "/FPGA_LED2_R") (class "Default")
      (node (ref "LED7") (pin "2") (pinfunction "2_2") (pintype "power_in"))
      (node (ref "LED7") (pin "3") (pinfunction "3_3") (pintype "power_in"))
      (node (ref "LEDS1") (pin "K2") (pinfunction "C_K2") (pintype "power_in"))
    )
    (net (code "6") (name "/FX3_LED_G") (class "Default")
      (node (ref "R169") (pin "1") (pinfunction "1_1") (pintype "passive"))
    )
    (net (code "7") (name "/FX3_LED_R") (class "Default")
      (node (ref "LED2") (pin "2") (pinfunction "2_2") (pintype "power_in"))
      (node (ref "LED2") (pin "3") (pinfunction "3_3") (pintype "power_in"))
      (node (ref "LEDS2") (pin "K1") (pinfunction "C_K1") (pintype "power_in"))
    )
    (net (code "8") (name "GND") (class "Default")
      (node (ref "C367") (pin "1") (pinfunction "1_1") (pintype "passive"))
      (node (ref "C368") (pin "1") (pinfunction "1_1") (pintype "passive"))
      (node (ref "C369") (pin "1") (pinfunction "1_1") (pintype "passive"))
      (node (ref "C370") (pin "1") (pinfunction "1_1") (pintype "passive"))
      (node (ref "C371") (pin "1") (pinfunction "1_1") (pintype "passive"))
      (node (ref "C372") (pin "2") (pinfunction "2_2") (pintype "passive"))
      (node (ref "C373") (pin "2") (pinfunction "2_2") (pintype "passive"))
      (node (ref "C374") (pin "1") (pinfunction "1_1") (pintype "passive"))
      (node (ref "C375") (pin "1") (pinfunction "1_1") (pintype "passive"))
      (node (ref "C376") (pin "1") (pinfunction "1_1") (pintype "passive"))
      (node (ref "C377") (pin "1") (pinfunction "1_1") (pintype "passive"))
      (node (ref "C379") (pin "1") (pinfunction "1_1") (pintype "passive"))
      (node (ref "C380") (pin "1") (pinfunction "1_1") (pintype "passive"))
      (node (ref "C381") (pin "2") (pinfunction "2_2") (pintype "passive"))
      (node (ref "C382") (pin "1") (pinfunction "1_1") (pintype "passive"))
      (node (ref "C383") (pin "1") (pinfunction "1_1") (pintype "passive"))
      (node (ref "C384") (pin "1") (pinfunction "1_1") (pintype "passive"))
      (node (ref "C385") (pin "1") (pinfunction "1_1") (pintype "passive"))
      (node (ref "C386") (pin "1") (pinfunction "1_1") (pintype "passive"))
      (node (ref "C387") (pin "1") (pinfunction "1_1") (pintype "passive"))
      (node (ref "C388") (pin "2") (pinfunction "2_2") (pintype "passive"))
      (node (ref "C389") (pin "2") (pinfunction "2_2") (pintype "passive"))
      (node (ref "C390") (pin "2") (pinfunction "2_2") (pintype "passive"))
      (node (ref "C391") (pin "2") (pinfunction "2_2") (pintype "passive"))
      (node (ref "C392") (pin "1") (pinfunction "1_1") (pintype "passive"))
      (node (ref "C393") (pin "1") (pinfunction "1_1") (pintype "passive"))
      (node (ref "C394") (pin "1") (pinfunction "1_1") (pintype "passive"))
      (node (ref "C395") (pin "2") (pinfunction "2_2") (pintype "passive"))
      (node (ref "C396") (pin "1") (pinfunction "1_1") (pintype "passive"))
      (node (ref "C397") (pin "1") (pinfunction "1_1") (pintype "passive"))
      (node (ref "C398") (pin "1") (pinfunction "1_1") (pintype "passive"))
      (node (ref "C400") (pin "1") (pinfunction "1_1") (pintype "passive"))
      (node (ref "C401") (pin "1") (pinfunction "1_1") (pintype "passive"))
      (node (ref "C402") (pin "1") (pinfunction "1_1") (pintype "passive"))
      (node (ref "C403") (pin "1") (pinfunction "1_1") (pintype "passive"))
      (node (ref "C404") (pin "1") (pinfunction "1_1") (pintype "passive"))
      (node (ref "C405") (pin "1") (pinfunction "1_1") (pintype "passive"))
      (node (ref "C406") (pin "1") (pinfunction "1_1") (pintype "passive"))
      (node (ref "C407") (pin "1") (pinfunction "1_1") (pintype "passive"))
      (node (ref "C408") (pin "2") (pinfunction "2_2") (pintype "passive"))
      (node (ref "C409") (pin "1") (pinfunction "1_1") (pintype "passive"))
      (node (ref "C410") (pin "1") (pinfunction "1_1") (pintype "passive"))
      (node (ref "C411") (pin "2") (pinfunction "2_2") (pintype "passive"))
      (node (ref "C412") (pin "2") (pinfunction "2_2") (pintype "passive"))
      (node (ref "C413") (pin "2") (pinfunction "2_2") (pintype "passive"))
      (node (ref "C414") (pin "1") (pinfunction "1_1") (pintype "passive"))
      (node (ref "C415") (pin "1") (pinfunction "1_1") (pintype "passive"))
      (node (ref "C416") (pin "1") (pinfunction "1_1") (pintype "passive"))
      (node (ref "C417") (pin "1") (pinfunction "1_1") (pintype "passive"))
      (node (ref "C418") (pin "1") (pinfunction "1_1") (pintype "passive"))
      (node (ref "C419") (pin "1") (pinfunction "1_1") (pintype "passive"))
      (node (ref "C420") (pin "1") (pinfunction "1_1") (pintype "passive"))
      (node (ref "C421") (pin "1") (pinfunction "1_1") (pintype "passive"))
      (node (ref "IC25") (pin "C2") (pinfunction "EN_C2") (pintype "passive"))
      (node (ref "IC25") (pin "D1") (pinfunction "GND_D1") (pintype "passive"))
      (node (ref "IC25") (pin "D2") (pinfunction "GND_D2") (pintype "passive"))
      (node (ref "IC25") (pin "D3") (pinfunction "DF_IN_D3") (pintype "passive"))
      (node (ref "IC26") (pin "4") (pinfunction "GND_4") (pintype "passive"))
      (node (ref "IC26") (pin "9") (pinfunction "PAD_9") (pintype "passive"))
      (node (ref "IC27") (pin "10") (pinfunction "PGND_10") (pintype "passive"))
      (node (ref "IC27") (pin "11") (pinfunction "PGND_11") (pintype "passive"))
      (node (ref "IC27") (pin "12") (pinfunction "PGND_12") (pintype "passive"))
      (node (ref "IC27") (pin "13") (pinfunction "PGND_13") (pintype "passive"))
      (node (ref "IC27") (pin "25") (pinfunction "GND_25") (pintype "passive"))
      (node (ref "IC27") (pin "4") (pinfunction "GND_4") (pintype "passive"))
      (node (ref "IC27") (pin "8") (pinfunction "PGND_8") (pintype "passive"))
      (node (ref "IC27") (pin "9") (pinfunction "PGND_9") (pintype "passive"))
      (node (ref "IC28") (pin "4") (pinfunction "GND_4") (pintype "passive"))
      (node (ref "IC28") (pin "9") (pinfunction "PAD_9") (pintype "passive"))
      (node (ref "IC29") (pin "11") (pinfunction "GND_11") (pintype "passive"))
      (node (ref "IC29") (pin "4") (pinfunction "PGND_4") (pintype "passive"))
      (node (ref "IC29") (pin "8") (pinfunction "GND_8") (pintype "passive"))
      (node (ref "IC30") (pin "4") (pinfunction "GND_4") (pintype "passive"))
      (node (ref "IC30") (pin "9") (pinfunction "PAD_9") (pintype "passive"))
      (node (ref "IC31") (pin "10") (pinfunction "PGND_10") (pintype "passive"))
      (node (ref "IC31") (pin "11") (pinfunction "PGND_11") (pintype "passive"))
      (node (ref "IC31") (pin "12") (pinfunction "PGND_12") (pintype "passive"))
      (node (ref "IC31") (pin "13") (pinfunction "PGND_13") (pintype "passive"))
      (node (ref "IC31") (pin "25") (pinfunction "GND_25") (pintype "passive"))
      (node (ref "IC31") (pin "4") (pinfunction "GND_4") (pintype "passive"))
      (node (ref "IC31") (pin "8") (pinfunction "PGND_8") (pintype "passive"))
      (node (ref "IC31") (pin "9") (pinfunction "PGND_9") (pintype "passive"))
      (node (ref "IC32") (pin "4") (pinfunction "GND_4") (pintype "passive"))
      (node (ref "IC32") (pin "9") (pinfunction "PAD_9") (pintype "passive"))
      (node (ref "IC33") (pin "4") (pinfunction "GND_4") (pintype "passive"))
      (node (ref "IC33") (pin "9") (pinfunction "PAD_9") (pintype "passive"))
      (node (ref "IC34") (pin "4") (pinfunction "GND_4") (pintype "passive"))
      (node (ref "IC34") (pin "9") (pinfunction "PAD_9") (pintype "passive"))
      (node (ref "IC35") (pin "3") (pinfunction "GND_3") (pintype "passive"))
      (node (ref "IC36") (pin "7") (pinfunction "GND_7") (pintype "passive"))
      (node (ref "IC36") (pin "9") (pinfunction "PAD_9") (pintype "passive"))
      (node (ref "J20") (pin "2") (pinfunction "2_2") (pintype "passive"))
      (node (ref "J20") (pin "3") (pinfunction "3_3") (pintype "passive"))
      (node (ref "J21") (pin "1") (pinfunction "1_1") (pintype "passive"))
      (node (ref "LED8") (pin "3") (pinfunction "3_3") (pintype "power_in"))
      (node (ref "LEDS2") (pin "K2") (pinfunction "C_K2") (pintype "power_in"))
      (node (ref "MECH1") (pin "MH1") (pinfunction "MH1_MH1") (pintype "passive"))
      (node (ref "MECH2") (pin "MH1") (pinfunction "MH1_MH1") (pintype "passive"))
      (node (ref "MECH3") (pin "MH1") (pinfunction "MH1_MH1") (pintype "passive"))
      (node (ref "MECH4") (pin "MH1") (pinfunction "MH1_MH1") (pintype "passive"))
      (node (ref "R175") (pin "2") (pinfunction "2_2") (pintype "passive"))
      (node (ref "R181") (pin "2") (pinfunction "2_2") (pintype "passive"))
      (node (ref "R182") (pin "2") (pinfunction "2_2") (pintype "passive"))
      (node (ref "R183") (pin "2") (pinfunction "2_2") (pintype "passive"))
      (node (ref "R184") (pin "1") (pinfunction "1_1") (pintype "passive"))
      (node (ref "R190") (pin "1") (pinfunction "1_1") (pintype "passive"))
      (node (ref "R196") (pin "2") (pinfunction "2_2") (pintype "passive"))
      (node (ref "R197") (pin "2") (pinfunction "2_2") (pintype "passive"))
      (node (ref "R198") (pin "1") (pinfunction "1_1") (pintype "passive"))
      (node (ref "R199") (pin "2") (pinfunction "2_2") (pintype "passive"))
      (node (ref "R200") (pin "2") (pinfunction "2_2") (pintype "passive"))
      (node (ref "R206") (pin "2") (pinfunction "2_2") (pintype "passive"))
      (node (ref "R207") (pin "2") (pinfunction "2_2") (pintype "passive"))
      (node (ref "R210") (pin "1") (pinfunction "1_1") (pintype "passive"))
    )
    (net (code "9") (name "Net-(C367-Pad2)") (class "Default")
      (node (ref "C367") (pin "2") (pinfunction "2_2") (pintype "passive"))
      (node (ref "FR56") (pin "2") (pinfunction "2_2") (pintype "passive"))
      (node (ref "IC25") (pin "A2") (pinfunction "Vout_A2") (pintype "passive"))
      (node (ref "IC25") (pin "A3") (pinfunction "Vout_A3") (pintype "passive"))
      (node (ref "IC25") (pin "B3") (pinfunction "Vout_B3") (pintype "passive"))
      (node (ref "IC25") (pin "C3") (pinfunction "Vout_C3") (pintype "passive"))
    )
    (net (code "10") (name "Net-(C373-Pad1)") (class "Default")
      (node (ref "C373") (pin "1") (pinfunction "1_1") (pintype "passive"))
      (node (ref "J20") (pin "1") (pinfunction "1_1") (pintype "passive"))
      (node (ref "J21") (pin "2") (pinfunction "2_2") (pintype "passive"))
      (node (ref "R172") (pin "2") (pinfunction "2_2") (pintype "passive"))
      (node (ref "VD1") (pin "A") (pinfunction "A_A") (pintype "passive"))
    )
    (net (code "11") (name "Net-(C378-Pad2)") (class "Default")
      (node (ref "C378") (pin "2") (pinfunction "2_2") (pintype "passive"))
      (node (ref "IC27") (pin "14") (pinfunction "SW_14") (pintype "passive"))
      (node (ref "IC27") (pin "26") (pinfunction "SW_26") (pintype "passive"))
      (node (ref "IC27") (pin "5") (pinfunction "SW_5") (pintype "passive"))
      (node (ref "IC27") (pin "6") (pinfunction "SW_6") (pintype "passive"))
      (node (ref "IC27") (pin "7") (pinfunction "SW_7") (pintype "passive"))
      (node (ref "L1") (pin "1") (pinfunction "1_1") (pintype "passive"))
    )
    (net (code "12") (name "Net-(C390-Pad1)") (class "Default")
      (node (ref "C390") (pin "1") (pinfunction "1_1") (pintype "passive"))
      (node (ref "R185") (pin "1") (pinfunction "1_1") (pintype "passive"))
    )
    (net (code "13") (name "Net-(C399-Pad2)") (class "Default")
      (node (ref "C399") (pin "2") (pinfunction "2_2") (pintype "passive"))
      (node (ref "IC31") (pin "14") (pinfunction "SW_14") (pintype "passive"))
      (node (ref "IC31") (pin "26") (pinfunction "SW_26") (pintype "passive"))
      (node (ref "IC31") (pin "5") (pinfunction "SW_5") (pintype "passive"))
      (node (ref "IC31") (pin "6") (pinfunction "SW_6") (pintype "passive"))
      (node (ref "IC31") (pin "7") (pinfunction "SW_7") (pintype "passive"))
      (node (ref "L2") (pin "1") (pinfunction "1_1") (pintype "passive"))
    )
    (net (code "14") (name "Net-(C412-Pad1)") (class "Default")
      (node (ref "C412") (pin "1") (pinfunction "1_1") (pintype "passive"))
      (node (ref "R201") (pin "1") (pinfunction "1_1") (pintype "passive"))
    )
    (net (code "15") (name "Net-(C418-Pad2)") (class "Default")
      (node (ref "C418") (pin "2") (pinfunction "2_2") (pintype "passive"))
      (node (ref "FR63") (pin "2") (pinfunction "2_2") (pintype "passive"))
      (node (ref "R208") (pin "2") (pinfunction "2_2") (pintype "passive"))
    )
    (net (code "16") (name "Net-(IC26-ADJ{slash}NC)") (class "Default")
      (node (ref "IC26") (pin "3") (pinfunction "ADJ/NC_3") (pintype "passive"))
      (node (ref "R174") (pin "1") (pinfunction "1_1") (pintype "passive"))
      (node (ref "R175") (pin "1") (pinfunction "1_1") (pintype "passive"))
    )
    (net (code "17") (name "Net-(IC26-OUT)") (class "Default")
      (node (ref "C377") (pin "2") (pinfunction "2_2") (pintype "passive"))
      (node (ref "IC26") (pin "1") (pinfunction "OUT_1") (pintype "output"))
      (node (ref "R173") (pin "2") (pinfunction "2_2") (pintype "passive"))
      (node (ref "R174") (pin "2") (pinfunction "2_2") (pintype "passive"))
    )
    (net (code "18") (name "Net-(IC27-BST)") (class "Default")
      (node (ref "C378") (pin "1") (pinfunction "1_1") (pintype "passive"))
      (node (ref "IC27") (pin "15") (pinfunction "BST_15") (pintype "passive"))
    )
    (net (code "19") (name "Net-(IC27-COMP)") (class "Default")
      (node (ref "C389") (pin "1") (pinfunction "1_1") (pintype "passive"))
      (node (ref "IC27") (pin "1") (pinfunction "COMP_1") (pintype "passive"))
      (node (ref "R185") (pin "2") (pinfunction "2_2") (pintype "passive"))
    )
    (net (code "20") (name "Net-(IC27-FB)") (class "Default")
      (node (ref "IC27") (pin "2") (pinfunction "FB_2") (pintype "passive"))
      (node (ref "R180") (pin "2") (pinfunction "2_2") (pintype "passive"))
      (node (ref "R184") (pin "2") (pinfunction "2_2") (pintype "passive"))
    )
    (net (code "21") (name "Net-(IC27-RT)") (class "Default")
      (node (ref "IC27") (pin "22") (pinfunction "RT_22") (pintype "passive"))
      (node (ref "R183") (pin "1") (pinfunction "1_1") (pintype "passive"))
    )
    (net (code "22") (name "Net-(IC27-SS)") (class "Default")
      (node (ref "C391") (pin "1") (pinfunction "1_1") (pintype "passive"))
      (node (ref "IC27") (pin "24") (pinfunction "SS_24") (pintype "passive"))
    )
    (net (code "23") (name "Net-(IC27-SYNC)") (class "Default")
      (node (ref "IC27") (pin "23") (pinfunction "SYNC_23") (pintype "passive"))
      (node (ref "R181") (pin "1") (pinfunction "1_1") (pintype "passive"))
    )
    (net (code "24") (name "Net-(IC27-VREG)") (class "Default")
      (node (ref "C388") (pin "1") (pinfunction "1_1") (pintype "passive"))
      (node (ref "IC27") (pin "3") (pinfunction "VREG_3") (pintype "passive"))
    )
    (net (code "25") (name "Net-(IC28-ADJ{slash}NC)") (class "Default")
      (node (ref "IC28") (pin "3") (pinfunction "ADJ/NC_3") (pintype "passive"))
      (node (ref "R179") (pin "1") (pinfunction "1_1") (pintype "passive"))
      (node (ref "R182") (pin "1") (pinfunction "1_1") (pintype "passive"))
    )
    (net (code "26") (name "Net-(IC28-EN)") (class "Default")
      (node (ref "C383") (pin "2") (pinfunction "2_2") (pintype "passive"))
      (node (ref "FR58") (pin "2") (pinfunction "2_2") (pintype "passive"))
      (node (ref "IC28") (pin "5") (pinfunction "EN_5") (pintype "input"))
      (node (ref "IC28") (pin "8") (pinfunction "IN_8") (pintype "input"))
    )
    (net (code "27") (name "Net-(IC28-OUT)") (class "Default")
      (node (ref "C384") (pin "2") (pinfunction "2_2") (pintype "passive"))
      (node (ref "IC28") (pin "1") (pinfunction "OUT_1") (pintype "output"))
      (node (ref "R178") (pin "2") (pinfunction "2_2") (pintype "passive"))
      (node (ref "R179") (pin "2") (pinfunction "2_2") (pintype "passive"))
    )
    (net (code "28") (name "Net-(IC29-S3)") (class "Default")
      (node (ref "IC29") (pin "7") (pinfunction "S3_7") (pintype "passive"))
      (node (ref "R187") (pin "2") (pinfunction "2_2") (pintype "passive"))
    )
    (net (code "29") (name "Net-(IC29-S5)") (class "Default")
      (node (ref "IC29") (pin "9") (pinfunction "S5_9") (pintype "passive"))
      (node (ref "R186") (pin "2") (pinfunction "2_2") (pintype "passive"))
    )
    (net (code "30") (name "Net-(IC30-ADJ{slash}NC)") (class "Default")
      (node (ref "IC30") (pin "3") (pinfunction "ADJ/NC_3") (pintype "passive"))
      (node (ref "R189") (pin "2") (pinfunction "2_2") (pintype "passive"))
      (node (ref "R190") (pin "2") (pinfunction "2_2") (pintype "passive"))
    )
    (net (code "31") (name "Net-(IC30-EN)") (class "Default")
      (node (ref "C397") (pin "2") (pinfunction "2_2") (pintype "passive"))
      (node (ref "FR59") (pin "2") (pinfunction "2_2") (pintype "passive"))
      (node (ref "IC30") (pin "5") (pinfunction "EN_5") (pintype "input"))
      (node (ref "IC30") (pin "8") (pinfunction "IN_8") (pintype "input"))
    )
    (net (code "32") (name "Net-(IC30-OUT)") (class "Default")
      (node (ref "C398") (pin "2") (pinfunction "2_2") (pintype "passive"))
      (node (ref "IC30") (pin "1") (pinfunction "OUT_1") (pintype "output"))
      (node (ref "R188") (pin "2") (pinfunction "2_2") (pintype "passive"))
      (node (ref "R189") (pin "1") (pinfunction "1_1") (pintype "passive"))
    )
    (net (code "33") (name "Net-(IC31-BST)") (class "Default")
      (node (ref "C399") (pin "1") (pinfunction "1_1") (pintype "passive"))
      (node (ref "IC31") (pin "15") (pinfunction "BST_15") (pintype "passive"))
    )
    (net (code "34") (name "Net-(IC31-COMP)") (class "Default")
      (node (ref "C411") (pin "1") (pinfunction "1_1") (pintype "passive"))
      (node (ref "IC31") (pin "1") (pinfunction "COMP_1") (pintype "passive"))
      (node (ref "R201") (pin "2") (pinfunction "2_2") (pintype "passive"))
    )
    (net (code "35") (name "Net-(IC31-FB)") (class "Default")
      (node (ref "IC31") (pin "2") (pinfunction "FB_2") (pintype "passive"))
      (node (ref "R195") (pin "2") (pinfunction "2_2") (pintype "passive"))
      (node (ref "R200") (pin "1") (pinfunction "1_1") (pintype "passive"))
    )
    (net (code "36") (name "Net-(IC31-RT)") (class "Default")
      (node (ref "IC31") (pin "22") (pinfunction "RT_22") (pintype "passive"))
      (node (ref "R199") (pin "1") (pinfunction "1_1") (pintype "passive"))
    )
    (net (code "37") (name "Net-(IC31-SS)") (class "Default")
      (node (ref "C413") (pin "1") (pinfunction "1_1") (pintype "passive"))
      (node (ref "IC31") (pin "24") (pinfunction "SS_24") (pintype "passive"))
    )
    (net (code "38") (name "Net-(IC31-SYNC)") (class "Default")
      (node (ref "IC31") (pin "23") (pinfunction "SYNC_23") (pintype "passive"))
      (node (ref "R196") (pin "1") (pinfunction "1_1") (pintype "passive"))
    )
    (net (code "39") (name "Net-(IC31-VREG)") (class "Default")
      (node (ref "C408") (pin "1") (pinfunction "1_1") (pintype "passive"))
      (node (ref "IC31") (pin "3") (pinfunction "VREG_3") (pintype "passive"))
    )
    (net (code "40") (name "Net-(IC32-ADJ{slash}NC)") (class "Default")
      (node (ref "IC32") (pin "3") (pinfunction "ADJ/NC_3") (pintype "passive"))
      (node (ref "R193") (pin "1") (pinfunction "1_1") (pintype "passive"))
      (node (ref "R197") (pin "1") (pinfunction "1_1") (pintype "passive"))
    )
    (net (code "41") (name "Net-(IC32-OUT)") (class "Default")
      (node (ref "C402") (pin "2") (pinfunction "2_2") (pintype "passive"))
      (node (ref "IC32") (pin "1") (pinfunction "OUT_1") (pintype "output"))
      (node (ref "R191") (pin "2") (pinfunction "2_2") (pintype "passive"))
      (node (ref "R193") (pin "2") (pinfunction "2_2") (pintype "passive"))
    )
    (net (code "42") (name "Net-(IC33-ADJ{slash}NC)") (class "Default")
      (node (ref "IC33") (pin "3") (pinfunction "ADJ/NC_3") (pintype "passive"))
      (node (ref "R194") (pin "1") (pinfunction "1_1") (pintype "passive"))
      (node (ref "R198") (pin "2") (pinfunction "2_2") (pintype "passive"))
    )
    (net (code "43") (name "Net-(IC33-EN)") (class "Default")
      (node (ref "C404") (pin "2") (pinfunction "2_2") (pintype "passive"))
      (node (ref "FR60") (pin "2") (pinfunction "2_2") (pintype "passive"))
      (node (ref "IC33") (pin "5") (pinfunction "EN_5") (pintype "input"))
      (node (ref "IC33") (pin "8") (pinfunction "IN_8") (pintype "input"))
    )
    (net (code "44") (name "Net-(IC33-OUT)") (class "Default")
      (node (ref "C405") (pin "2") (pinfunction "2_2") (pintype "passive"))
      (node (ref "IC33") (pin "1") (pinfunction "OUT_1") (pintype "output"))
      (node (ref "R192") (pin "2") (pinfunction "2_2") (pintype "passive"))
      (node (ref "R194") (pin "2") (pinfunction "2_2") (pintype "passive"))
    )
    (net (code "45") (name "Net-(IC34-ADJ{slash}NC)") (class "Default")
      (node (ref "IC34") (pin "3") (pinfunction "ADJ/NC_3") (pintype "passive"))
      (node (ref "R203") (pin "1") (pinfunction "1_1") (pintype "passive"))
      (node (ref "R206") (pin "1") (pinfunction "1_1") (pintype "passive"))
    )
    (net (code "46") (name "Net-(IC34-OUT)") (class "Default")
      (node (ref "C410") (pin "2") (pinfunction "2_2") (pintype "passive"))
      (node (ref "IC34") (pin "1") (pinfunction "OUT_1") (pintype "output"))
      (node (ref "R202") (pin "2") (pinfunction "2_2") (pintype "passive"))
      (node (ref "R203") (pin "2") (pinfunction "2_2") (pintype "passive"))
    )
    (net (code "47") (name "Net-(IC35-ADJUST)") (class "Default")
      (node (ref "IC35") (pin "5") (pinfunction "ADJUST_5") (pintype "passive"))
      (node (ref "R205") (pin "2") (pinfunction "2_2") (pintype "passive"))
      (node (ref "R207") (pin "1") (pinfunction "1_1") (pintype "passive"))
    )
    (net (code "48") (name "Net-(IC35-IN)") (class "Default")
      (node (ref "C416") (pin "2") (pinfunction "2_2") (pintype "passive"))
      (node (ref "FR61") (pin "2") (pinfunction "2_2") (pintype "passive"))
      (node (ref "IC35") (pin "2") (pinfunction "IN_2") (pintype "passive"))
    )
    (net (code "49") (name "Net-(IC35-OUT)") (class "Default")
      (node (ref "C415") (pin "2") (pinfunction "2_2") (pintype "passive"))
      (node (ref "IC35") (pin "4") (pinfunction "OUT_4") (pintype "passive"))
      (node (ref "R204") (pin "2") (pinfunction "2_2") (pintype "passive"))
      (node (ref "R205") (pin "1") (pinfunction "1_1") (pintype "passive"))
    )
    (net (code "50") (name "Net-(IC36-ADJ{slash}BYP)") (class "Default")
      (node (ref "IC36") (pin "8") (pinfunction "ADJ/BYP_8") (pintype "input"))
      (node (ref "R209") (pin "2") (pinfunction "2_2") (pintype "passive"))
      (node (ref "R210") (pin "2") (pinfunction "2_2") (pintype "passive"))
    )
    (net (code "51") (name "Net-(IC36-EN)") (class "Default")
      (node (ref "C421") (pin "2") (pinfunction "2_2") (pintype "passive"))
      (node (ref "IC36") (pin "1") (pinfunction "EN_1") (pintype "input"))
      (node (ref "R211") (pin "2") (pinfunction "2_2") (pintype "passive"))
      (node (ref "R212") (pin "1") (pinfunction "1_1") (pintype "passive"))
    )
    (net (code "52") (name "Net-(IC36-VIN)") (class "Default")
      (node (ref "C420") (pin "2") (pinfunction "2_2") (pintype "passive"))
      (node (ref "FR62") (pin "2") (pinfunction "2_2") (pintype "passive"))
      (node (ref "IC36") (pin "3") (pinfunction "VIN_3") (pintype "input"))
    )
    (net (code "53") (name "Net-(IC36-VOUT)") (class "Default")
      (node (ref "C417") (pin "2") (pinfunction "2_2") (pintype "passive"))
      (node (ref "FR63") (pin "1") (pinfunction "1_1") (pintype "passive"))
      (node (ref "IC36") (pin "5") (pinfunction "VOUT_5") (pintype "output"))
      (node (ref "R209") (pin "1") (pinfunction "1_1") (pintype "passive"))
    )
    (net (code "54") (name "Net-(LED1-Pad1)") (class "Default")
      (node (ref "LED1") (pin "1") (pinfunction "1_1") (pintype "power_in"))
      (node (ref "LED1") (pin "4") (pinfunction "4_4") (pintype "power_in"))
      (node (ref "LEDS1") (pin "A1") (pinfunction "A_A1") (pintype "power_in"))
      (node (ref "R168") (pin "2") (pinfunction "2_2") (pintype "passive"))
    )
    (net (code "55") (name "Net-(LED2-Pad1)") (class "Default")
      (node (ref "LED2") (pin "1") (pinfunction "1_1") (pintype "power_in"))
      (node (ref "LED2") (pin "4") (pinfunction "4_4") (pintype "power_in"))
      (node (ref "LEDS2") (pin "A1") (pinfunction "A_A1") (pintype "power_in"))
      (node (ref "R169") (pin "2") (pinfunction "2_2") (pintype "passive"))
    )
    (net (code "56") (name "Net-(LED7-Pad1)") (class "Default")
      (node (ref "LED7") (pin "1") (pinfunction "1_1") (pintype "power_in"))
      (node (ref "LED7") (pin "4") (pinfunction "4_4") (pintype "power_in"))
      (node (ref "LEDS1") (pin "A2") (pinfunction "A_A2") (pintype "power_in"))
      (node (ref "R170") (pin "2") (pinfunction "2_2") (pintype "passive"))
    )
    (net (code "57") (name "Net-(LED8-Pad1)") (class "Default")
      (node (ref "LED8") (pin "1") (pinfunction "1_1") (pintype "power_in"))
      (node (ref "LEDS2") (pin "A2") (pinfunction "A_A2") (pintype "power_in"))
      (node (ref "R171") (pin "2") (pinfunction "2_2") (pintype "passive"))
    )
    (net (code "58") (name "VCC1P2") (class "Default")
      (node (ref "C406") (pin "2") (pinfunction "2_2") (pintype "passive"))
      (node (ref "C407") (pin "2") (pinfunction "2_2") (pintype "passive"))
      (node (ref "L2") (pin "2") (pinfunction "2_2") (pintype "passive"))
      (node (ref "R195") (pin "1") (pinfunction "1_1") (pintype "passive"))
    )
    (net (code "59") (name "VCC1P4_LMS") (class "Default")
      (node (ref "R188") (pin "1") (pinfunction "1_1") (pintype "passive"))
    )
    (net (code "60") (name "VCC1P8") (class "Default")
      (node (ref "R202") (pin "1") (pinfunction "1_1") (pintype "passive"))
    )
    (net (code "61") (name "VCC1P8_DDR2") (class "Default")
      (node (ref "C387") (pin "2") (pinfunction "2_2") (pintype "passive"))
      (node (ref "IC29") (pin "1") (pinfunction "VDDQSNS_1") (pintype "passive"))
      (node (ref "IC29") (pin "2") (pinfunction "VLDOIN_2") (pintype "passive"))
      (node (ref "R191") (pin "1") (pinfunction "1_1") (pintype "passive"))
    )
    (net (code "62") (name "VCC1P8_LMS") (class "Default")
      (node (ref "R178") (pin "1") (pinfunction "1_1") (pintype "passive"))
    )
    (net (code "63") (name "VCC1P25_LMS") (class "Default")
      (node (ref "R192") (pin "1") (pinfunction "1_1") (pintype "passive"))
    )
    (net (code "64") (name "VCC1P25_LMS_DIG") (class "Default")
      (node (ref "R204") (pin "1") (pinfunction "1_1") (pintype "passive"))
    )
    (net (code "65") (name "VCC2P5") (class "Default")
      (node (ref "R173") (pin "1") (pinfunction "1_1") (pintype "passive"))
      (node (ref "R177") (pin "2") (pinfunction "2_2") (pintype "passive"))
      (node (ref "R211") (pin "1") (pinfunction "1_1") (pintype "passive"))
    )
    (net (code "66") (name "VCC3P3") (class "Default")
      (node (ref "C376") (pin "2") (pinfunction "2_2") (pintype "passive"))
      (node (ref "C382") (pin "2") (pinfunction "2_2") (pintype "passive"))
      (node (ref "C385") (pin "2") (pinfunction "2_2") (pintype "passive"))
      (node (ref "C386") (pin "2") (pinfunction "2_2") (pintype "passive"))
      (node (ref "C394") (pin "2") (pinfunction "2_2") (pintype "passive"))
      (node (ref "C396") (pin "2") (pinfunction "2_2") (pintype "passive"))
      (node (ref "C401") (pin "2") (pinfunction "2_2") (pintype "passive"))
      (node (ref "C403") (pin "2") (pinfunction "2_2") (pintype "passive"))
      (node (ref "C409") (pin "2") (pinfunction "2_2") (pintype "passive"))
      (node (ref "C414") (pin "2") (pinfunction "2_2") (pintype "passive"))
      (node (ref "FR58") (pin "1") (pinfunction "1_1") (pintype "passive"))
      (node (ref "FR59") (pin "1") (pinfunction "1_1") (pintype "passive"))
      (node (ref "FR60") (pin "1") (pinfunction "1_1") (pintype "passive"))
      (node (ref "FR61") (pin "1") (pinfunction "1_1") (pintype "passive"))
      (node (ref "IC26") (pin "5") (pinfunction "EN_5") (pintype "input"))
      (node (ref "IC26") (pin "8") (pinfunction "IN_8") (pintype "input"))
      (node (ref "IC29") (pin "10") (pinfunction "VIN_10") (pintype "passive"))
      (node (ref "IC32") (pin "5") (pinfunction "EN_5") (pintype "input"))
      (node (ref "IC32") (pin "8") (pinfunction "IN_8") (pintype "input"))
      (node (ref "IC34") (pin "5") (pinfunction "EN_5") (pintype "input"))
      (node (ref "IC34") (pin "8") (pinfunction "IN_8") (pintype "input"))
      (node (ref "L1") (pin "2") (pinfunction "2_2") (pintype "passive"))
      (node (ref "R171") (pin "1") (pinfunction "1_1") (pintype "passive"))
      (node (ref "R176") (pin "2") (pinfunction "2_2") (pintype "passive"))
      (node (ref "R180") (pin "1") (pinfunction "1_1") (pintype "passive"))
      (node (ref "R186") (pin "1") (pinfunction "1_1") (pintype "passive"))
      (node (ref "R187") (pin "1") (pinfunction "1_1") (pintype "passive"))
    )
    (net (code "67") (name "VCC3P3_CLK") (class "Default")
      (node (ref "R208") (pin "1") (pinfunction "1_1") (pintype "passive"))
    )
    (net (code "68") (name "VCC5P0_USB") (class "Default")
      (node (ref "C375") (pin "2") (pinfunction "2_2") (pintype "passive"))
      (node (ref "IC25") (pin "A1") (pinfunction "Vbus_A1") (pintype "passive"))
      (node (ref "IC25") (pin "B1") (pinfunction "Vbus_B1") (pintype "passive"))
      (node (ref "IC25") (pin "C1") (pinfunction "Vbus_C1") (pintype "passive"))
      (node (ref "R167") (pin "2") (pinfunction "2_2") (pintype "passive"))
    )
    (net (code "69") (name "VCC_EXT") (class "Default")
      (node (ref "C374") (pin "2") (pinfunction "2_2") (pintype "passive"))
      (node (ref "IC25") (pin "A4") (pinfunction "Vin_A4") (pintype "passive"))
      (node (ref "IC25") (pin "B4") (pinfunction "Vin_B4") (pintype "passive"))
      (node (ref "IC25") (pin "C4") (pinfunction "Vin_C4") (pintype "passive"))
      (node (ref "R166") (pin "2") (pinfunction "2_2") (pintype "passive"))
      (node (ref "R172") (pin "1") (pinfunction "1_1") (pintype "passive"))
      (node (ref "VD1") (pin "K") (pinfunction "K_K") (pintype "passive"))
    )
    (net (code "70") (name "VCC_INT") (class "Default")
      (node (ref "C368") (pin "2") (pinfunction "2_2") (pintype "passive"))
      (node (ref "C369") (pin "2") (pinfunction "2_2") (pintype "passive"))
      (node (ref "C370") (pin "2") (pinfunction "2_2") (pintype "passive"))
      (node (ref "C371") (pin "2") (pinfunction "2_2") (pintype "passive"))
      (node (ref "C372") (pin "1") (pinfunction "1_1") (pintype "passive"))
      (node (ref "C379") (pin "2") (pinfunction "2_2") (pintype "passive"))
      (node (ref "C400") (pin "2") (pinfunction "2_2") (pintype "passive"))
      (node (ref "C419") (pin "2") (pinfunction "2_2") (pintype "passive"))
      (node (ref "FR56") (pin "1") (pinfunction "1_1") (pintype "passive"))
      (node (ref "FR62") (pin "1") (pinfunction "1_1") (pintype "passive"))
      (node (ref "IC27") (pin "16") (pinfunction "PVIN_16") (pintype "passive"))
      (node (ref "IC27") (pin "17") (pinfunction "PVIN_17") (pintype "passive"))
      (node (ref "IC27") (pin "18") (pinfunction "PVIN_18") (pintype "passive"))
      (node (ref "IC27") (pin "19") (pinfunction "PVIN_19") (pintype "passive"))
      (node (ref "IC27") (pin "20") (pinfunction "EN_20") (pintype "passive"))
      (node (ref "IC31") (pin "16") (pinfunction "PVIN_16") (pintype "passive"))
      (node (ref "IC31") (pin "17") (pinfunction "PVIN_17") (pintype "passive"))
      (node (ref "IC31") (pin "18") (pinfunction "PVIN_18") (pintype "passive"))
      (node (ref "IC31") (pin "19") (pinfunction "PVIN_19") (pintype "passive"))
      (node (ref "IC31") (pin "20") (pinfunction "EN_20") (pintype "passive"))
      (node (ref "J21") (pin "3") (pinfunction "3_3") (pintype "passive"))
      (node (ref "R166") (pin "1") (pinfunction "1_1") (pintype "passive"))
      (node (ref "R167") (pin "1") (pinfunction "1_1") (pintype "passive"))
    )
    (net (code "71") (name "VDIO_LMS") (class "Default")
      (node (ref "C380") (pin "2") (pinfunction "2_2") (pintype "passive"))
      (node (ref "C381") (pin "1") (pinfunction "1_1") (pintype "passive"))
      (node (ref "FR57") (pin "2") (pinfunction "2_2") (pintype "passive"))
    )
    (net (code "72") (name "VDIO_LMS_FPGA") (class "Default")
      (node (ref "FR57") (pin "1") (pinfunction "1_1") (pintype "passive"))
      (node (ref "R176") (pin "1") (pinfunction "1_1") (pintype "passive"))
      (node (ref "R177") (pin "1") (pinfunction "1_1") (pintype "passive"))
      (node (ref "R212") (pin "2") (pinfunction "2_2") (pintype "passive"))
    )
    (net (code "73") (name "VREF_DDR2") (class "Default")
      (node (ref "C395") (pin "1") (pinfunction "1_1") (pintype "passive"))
      (node (ref "IC29") (pin "6") (pinfunction "VTTREF_6") (pintype "passive"))
    )
    (net (code "74") (name "VTT_DDR2") (class "Default")
      (node (ref "C392") (pin "2") (pinfunction "2_2") (pintype "passive"))
      (node (ref "C393") (pin "2") (pinfunction "2_2") (pintype "passive"))
      (node (ref "IC29") (pin "3") (pinfunction "VTT_3") (pintype "passive"))
      (node (ref "IC29") (pin "5") (pinfunction "VTTSNS_5") (pintype "passive"))
    )
    (net (code "75") (name "unconnected-(F1-Pad1)") (class "Default")
      (node (ref "F1") (pin "1") (pintype "passive+no_connect"))
    )
    (net (code "76") (name "unconnected-(F2-Pad1)") (class "Default")
      (node (ref "F2") (pin "1") (pintype "passive+no_connect"))
    )
    (net (code "77") (name "unconnected-(F3-Pad1)") (class "Default")
      (node (ref "F3") (pin "1") (pintype "passive+no_connect"))
    )
    (net (code "78") (name "unconnected-(F4-Pad1)") (class "Default")
      (node (ref "F4") (pin "1") (pintype "passive+no_connect"))
    )
    (net (code "79") (name "unconnected-(IC25-Other_Vin_AVA-PadB2)") (class "Default")
      (node (ref "IC25") (pin "B2") (pinfunction "Other_Vin_AVA_B2") (pintype "passive+no_connect"))
    )
    (net (code "80") (name "unconnected-(IC26-NC-Pad2)") (class "Default")
      (node (ref "IC26") (pin "2") (pinfunction "NC_2") (pintype "passive+no_connect"))
    )
    (net (code "81") (name "unconnected-(IC26-NC-Pad6)") (class "Default")
      (node (ref "IC26") (pin "6") (pinfunction "NC_6") (pintype "passive+no_connect"))
    )
    (net (code "82") (name "unconnected-(IC26-NC-Pad7)") (class "Default")
      (node (ref "IC26") (pin "7") (pinfunction "NC_7") (pintype "passive+no_connect"))
    )
    (net (code "83") (name "unconnected-(IC27-PGOOD-Pad21)") (class "Default")
      (node (ref "IC27") (pin "21") (pinfunction "PGOOD_21") (pintype "passive+no_connect"))
    )
    (net (code "84") (name "unconnected-(IC28-NC-Pad2)") (class "Default")
      (node (ref "IC28") (pin "2") (pinfunction "NC_2") (pintype "passive+no_connect"))
    )
    (net (code "85") (name "unconnected-(IC28-NC-Pad6)") (class "Default")
      (node (ref "IC28") (pin "6") (pinfunction "NC_6") (pintype "passive+no_connect"))
    )
    (net (code "86") (name "unconnected-(IC28-NC-Pad7)") (class "Default")
      (node (ref "IC28") (pin "7") (pinfunction "NC_7") (pintype "passive+no_connect"))
    )
    (net (code "87") (name "unconnected-(IC30-NC-Pad2)") (class "Default")
      (node (ref "IC30") (pin "2") (pinfunction "NC_2") (pintype "passive+no_connect"))
    )
    (net (code "88") (name "unconnected-(IC30-NC-Pad6)") (class "Default")
      (node (ref "IC30") (pin "6") (pinfunction "NC_6") (pintype "passive+no_connect"))
    )
    (net (code "89") (name "unconnected-(IC30-NC-Pad7)") (class "Default")
      (node (ref "IC30") (pin "7") (pinfunction "NC_7") (pintype "passive+no_connect"))
    )
    (net (code "90") (name "unconnected-(IC31-PGOOD-Pad21)") (class "Default")
      (node (ref "IC31") (pin "21") (pinfunction "PGOOD_21") (pintype "passive+no_connect"))
    )
    (net (code "91") (name "unconnected-(IC32-NC-Pad2)") (class "Default")
      (node (ref "IC32") (pin "2") (pinfunction "NC_2") (pintype "passive+no_connect"))
    )
    (net (code "92") (name "unconnected-(IC32-NC-Pad6)") (class "Default")
      (node (ref "IC32") (pin "6") (pinfunction "NC_6") (pintype "passive+no_connect"))
    )
    (net (code "93") (name "unconnected-(IC32-NC-Pad7)") (class "Default")
      (node (ref "IC32") (pin "7") (pinfunction "NC_7") (pintype "passive+no_connect"))
    )
    (net (code "94") (name "unconnected-(IC33-NC-Pad2)") (class "Default")
      (node (ref "IC33") (pin "2") (pinfunction "NC_2") (pintype "passive+no_connect"))
    )
    (net (code "95") (name "unconnected-(IC33-NC-Pad6)") (class "Default")
      (node (ref "IC33") (pin "6") (pinfunction "NC_6") (pintype "passive+no_connect"))
    )
    (net (code "96") (name "unconnected-(IC33-NC-Pad7)") (class "Default")
      (node (ref "IC33") (pin "7") (pinfunction "NC_7") (pintype "passive+no_connect"))
    )
    (net (code "97") (name "unconnected-(IC34-NC-Pad2)") (class "Default")
      (node (ref "IC34") (pin "2") (pinfunction "NC_2") (pintype "passive+no_connect"))
    )
    (net (code "98") (name "unconnected-(IC34-NC-Pad6)") (class "Default")
      (node (ref "IC34") (pin "6") (pinfunction "NC_6") (pintype "passive+no_connect"))
    )
    (net (code "99") (name "unconnected-(IC34-NC-Pad7)") (class "Default")
      (node (ref "IC34") (pin "7") (pinfunction "NC_7") (pintype "passive+no_connect"))
    )
    (net (code "100") (name "unconnected-(IC35-NC-Pad1)") (class "Default")
      (node (ref "IC35") (pin "1") (pinfunction "NC_1") (pintype "passive+no_connect"))
    )
    (net (code "101") (name "unconnected-(IC36-NC-Pad2)") (class "Default")
      (node (ref "IC36") (pin "2") (pinfunction "NC_2") (pintype "passive+no_connect"))
    )
    (net (code "102") (name "unconnected-(IC36-NC-Pad4)") (class "Default")
      (node (ref "IC36") (pin "4") (pinfunction "NC_4") (pintype "passive+no_connect"))
    )
    (net (code "103") (name "unconnected-(IC36-NC-Pad6)") (class "Default")
      (node (ref "IC36") (pin "6") (pinfunction "NC_6") (pintype "passive+no_connect"))
    )
    (net (code "104") (name "unconnected-(LED3-C-PadK)") (class "Default")
      (node (ref "LED3") (pin "K") (pinfunction "C_K") (pintype "power_in+no_connect"))
    )
    (net (code "105") (name "unconnected-(LED3-PadA)") (class "Default")
      (node (ref "LED3") (pin "A") (pinfunction "A_A") (pintype "power_in+no_connect"))
    )
    (net (code "106") (name "unconnected-(LED4-C-PadK)") (class "Default")
      (node (ref "LED4") (pin "K") (pinfunction "C_K") (pintype "power_in+no_connect"))
    )
    (net (code "107") (name "unconnected-(LED4-PadA)") (class "Default")
      (node (ref "LED4") (pin "A") (pinfunction "A_A") (pintype "power_in+no_connect"))
    )
    (net (code "108") (name "unconnected-(LED5-C-PadK)") (class "Default")
      (node (ref "LED5") (pin "K") (pinfunction "C_K") (pintype "power_in+no_connect"))
    )
    (net (code "109") (name "unconnected-(LED5-PadA)") (class "Default")
      (node (ref "LED5") (pin "A") (pinfunction "A_A") (pintype "power_in+no_connect"))
    )
    (net (code "110") (name "unconnected-(LED6-C-PadK)") (class "Default")
      (node (ref "LED6") (pin "K") (pinfunction "C_K") (pintype "power_in+no_connect"))
    )
    (net (code "111") (name "unconnected-(LED6-PadA)") (class "Default")
      (node (ref "LED6") (pin "A") (pinfunction "A_A") (pintype "power_in+no_connect"))
    )
    (net (code "112") (name "unconnected-(LED8-Pad2)") (class "Default")
      (node (ref "LED8") (pin "2") (pinfunction "2_2") (pintype "power_in+no_connect"))
    )
    (net (code "113") (name "unconnected-(LED8-Pad4)") (class "Default")
      (node (ref "LED8") (pin "4") (pinfunction "4_4") (pintype "power_in+no_connect"))
    )
  )
)
